# ButtonsLEDs.net
KiCad netlist of a schematic drawn in EAGLE
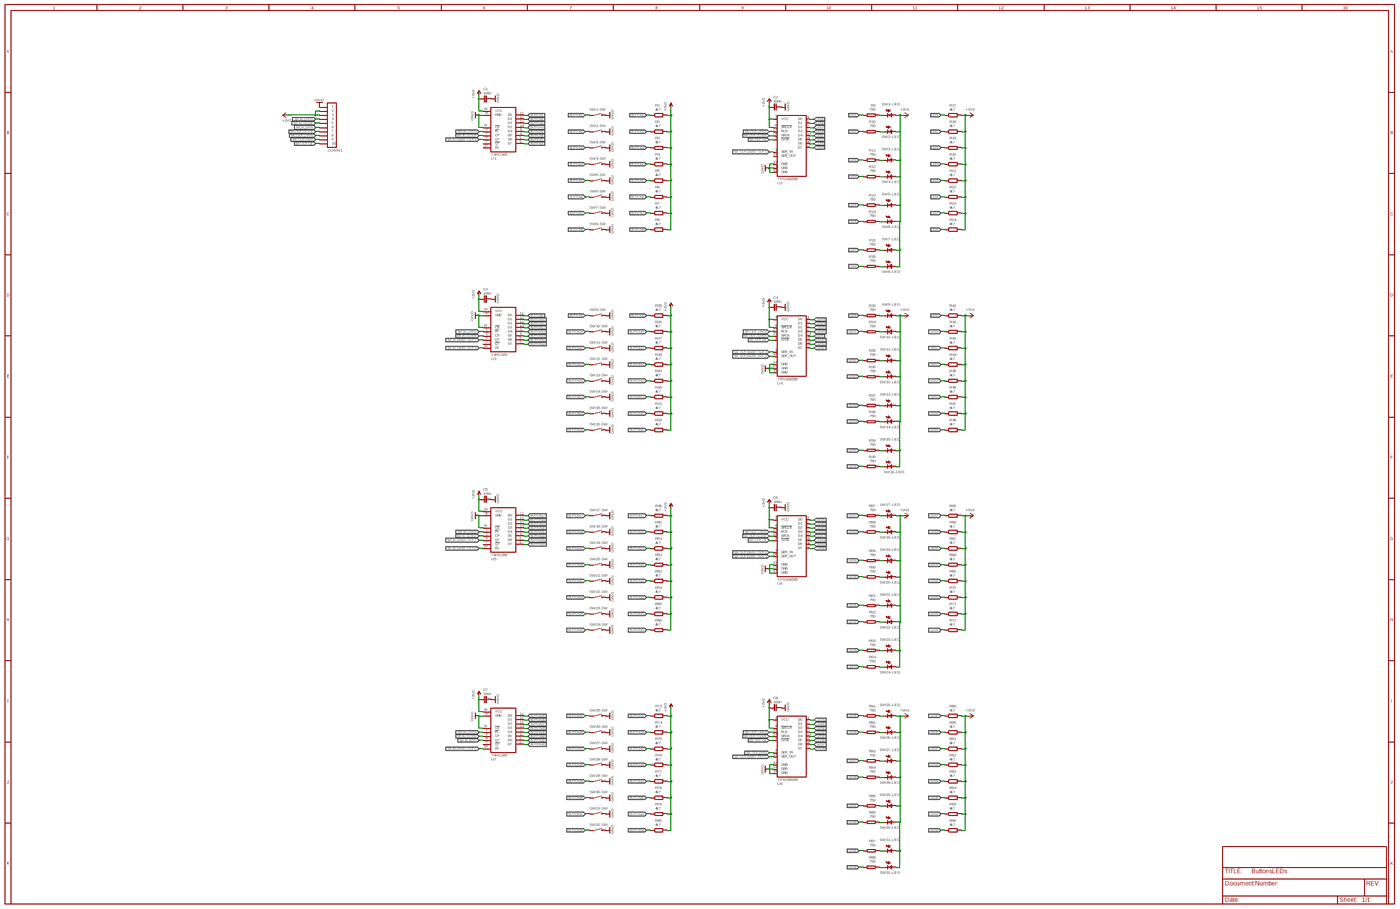
[diagram p0: schematic, sheet 1, overview]
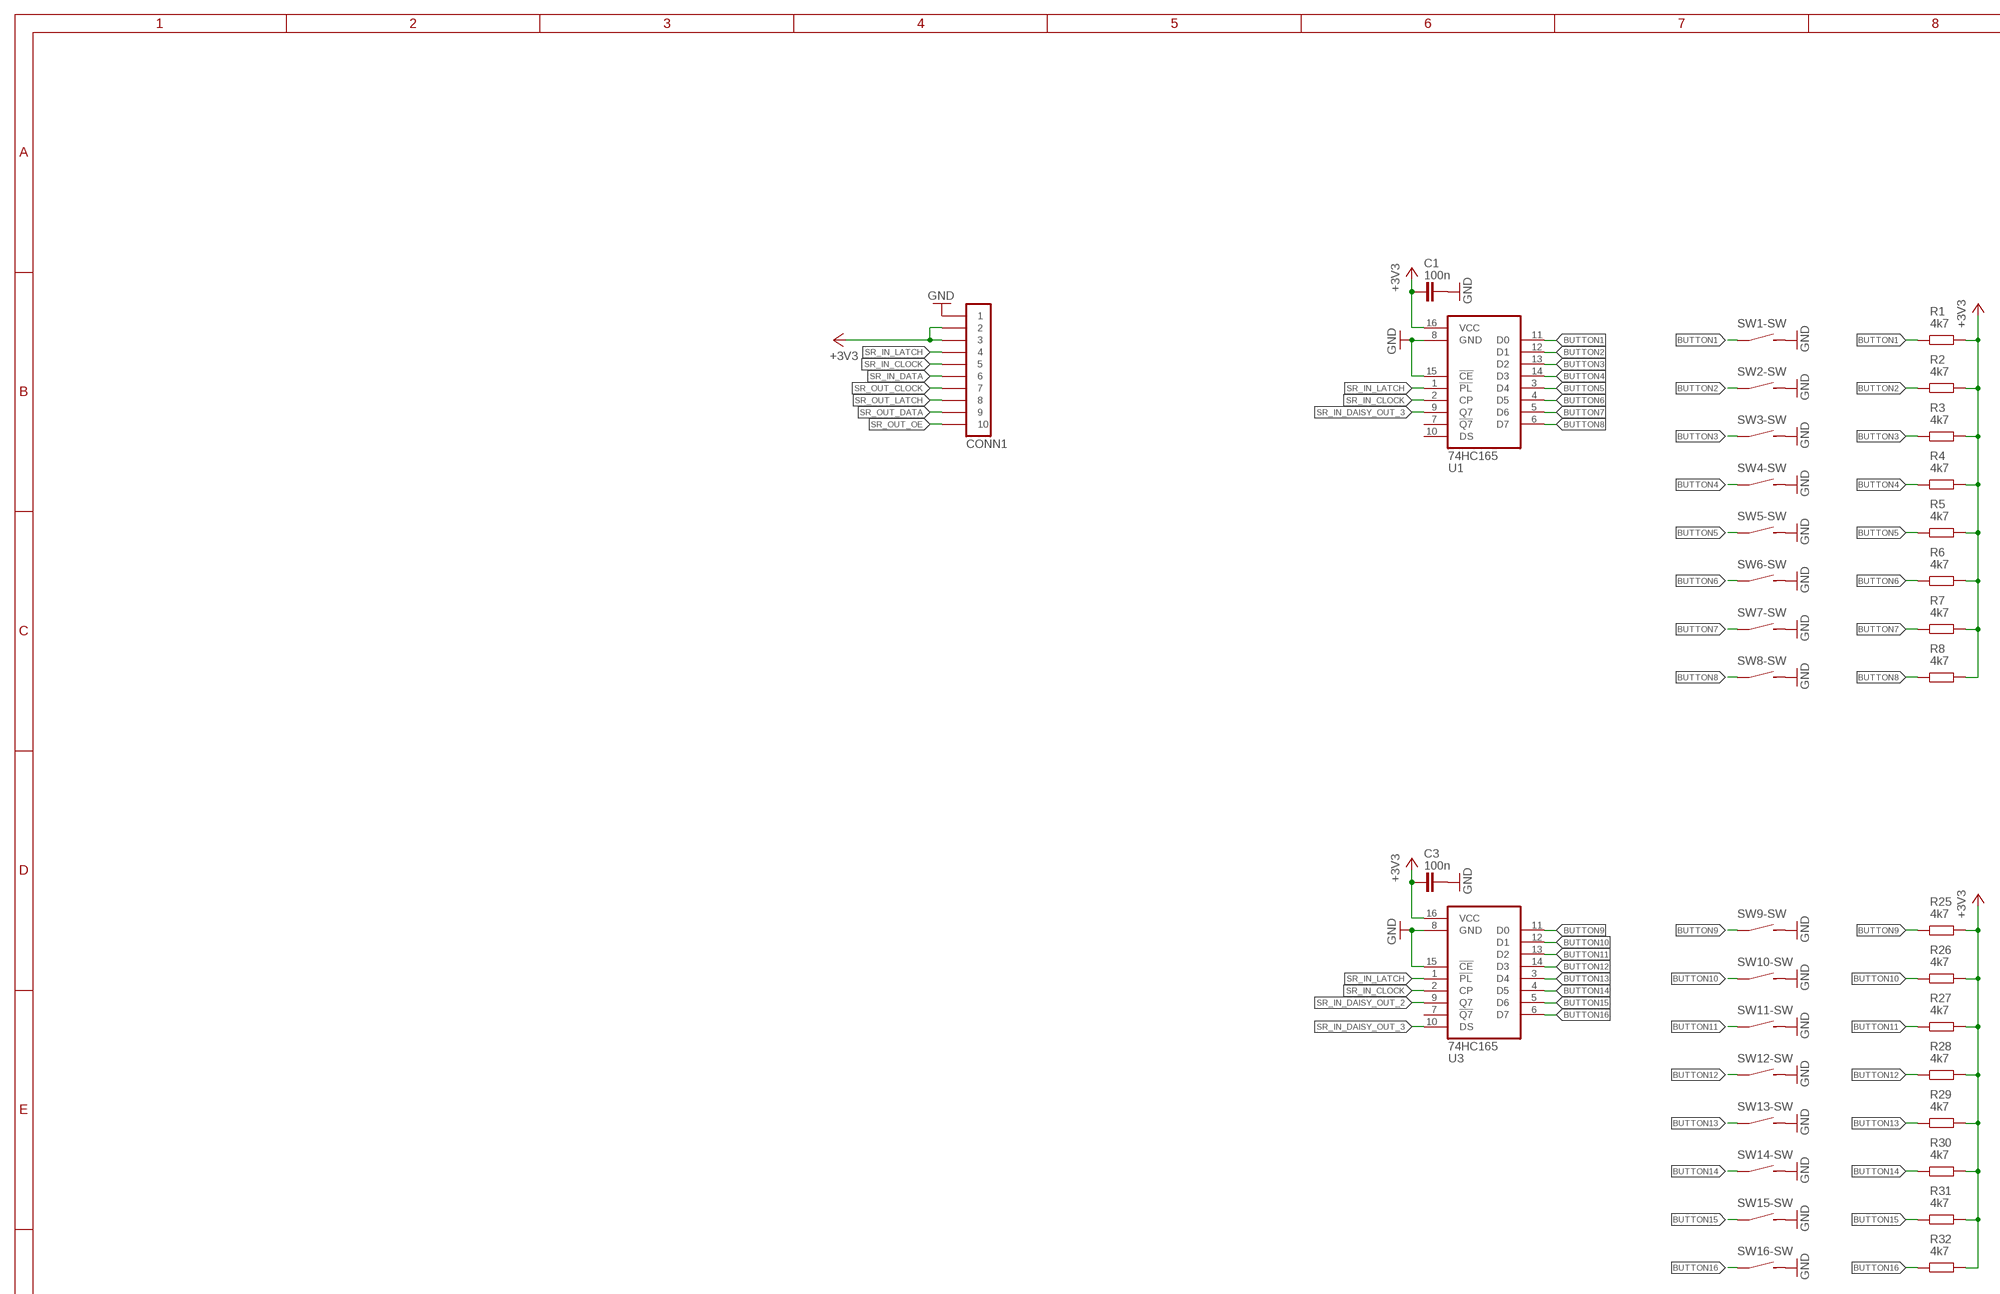
[diagram p1: schematic, sheet 1, part 1 of 4]
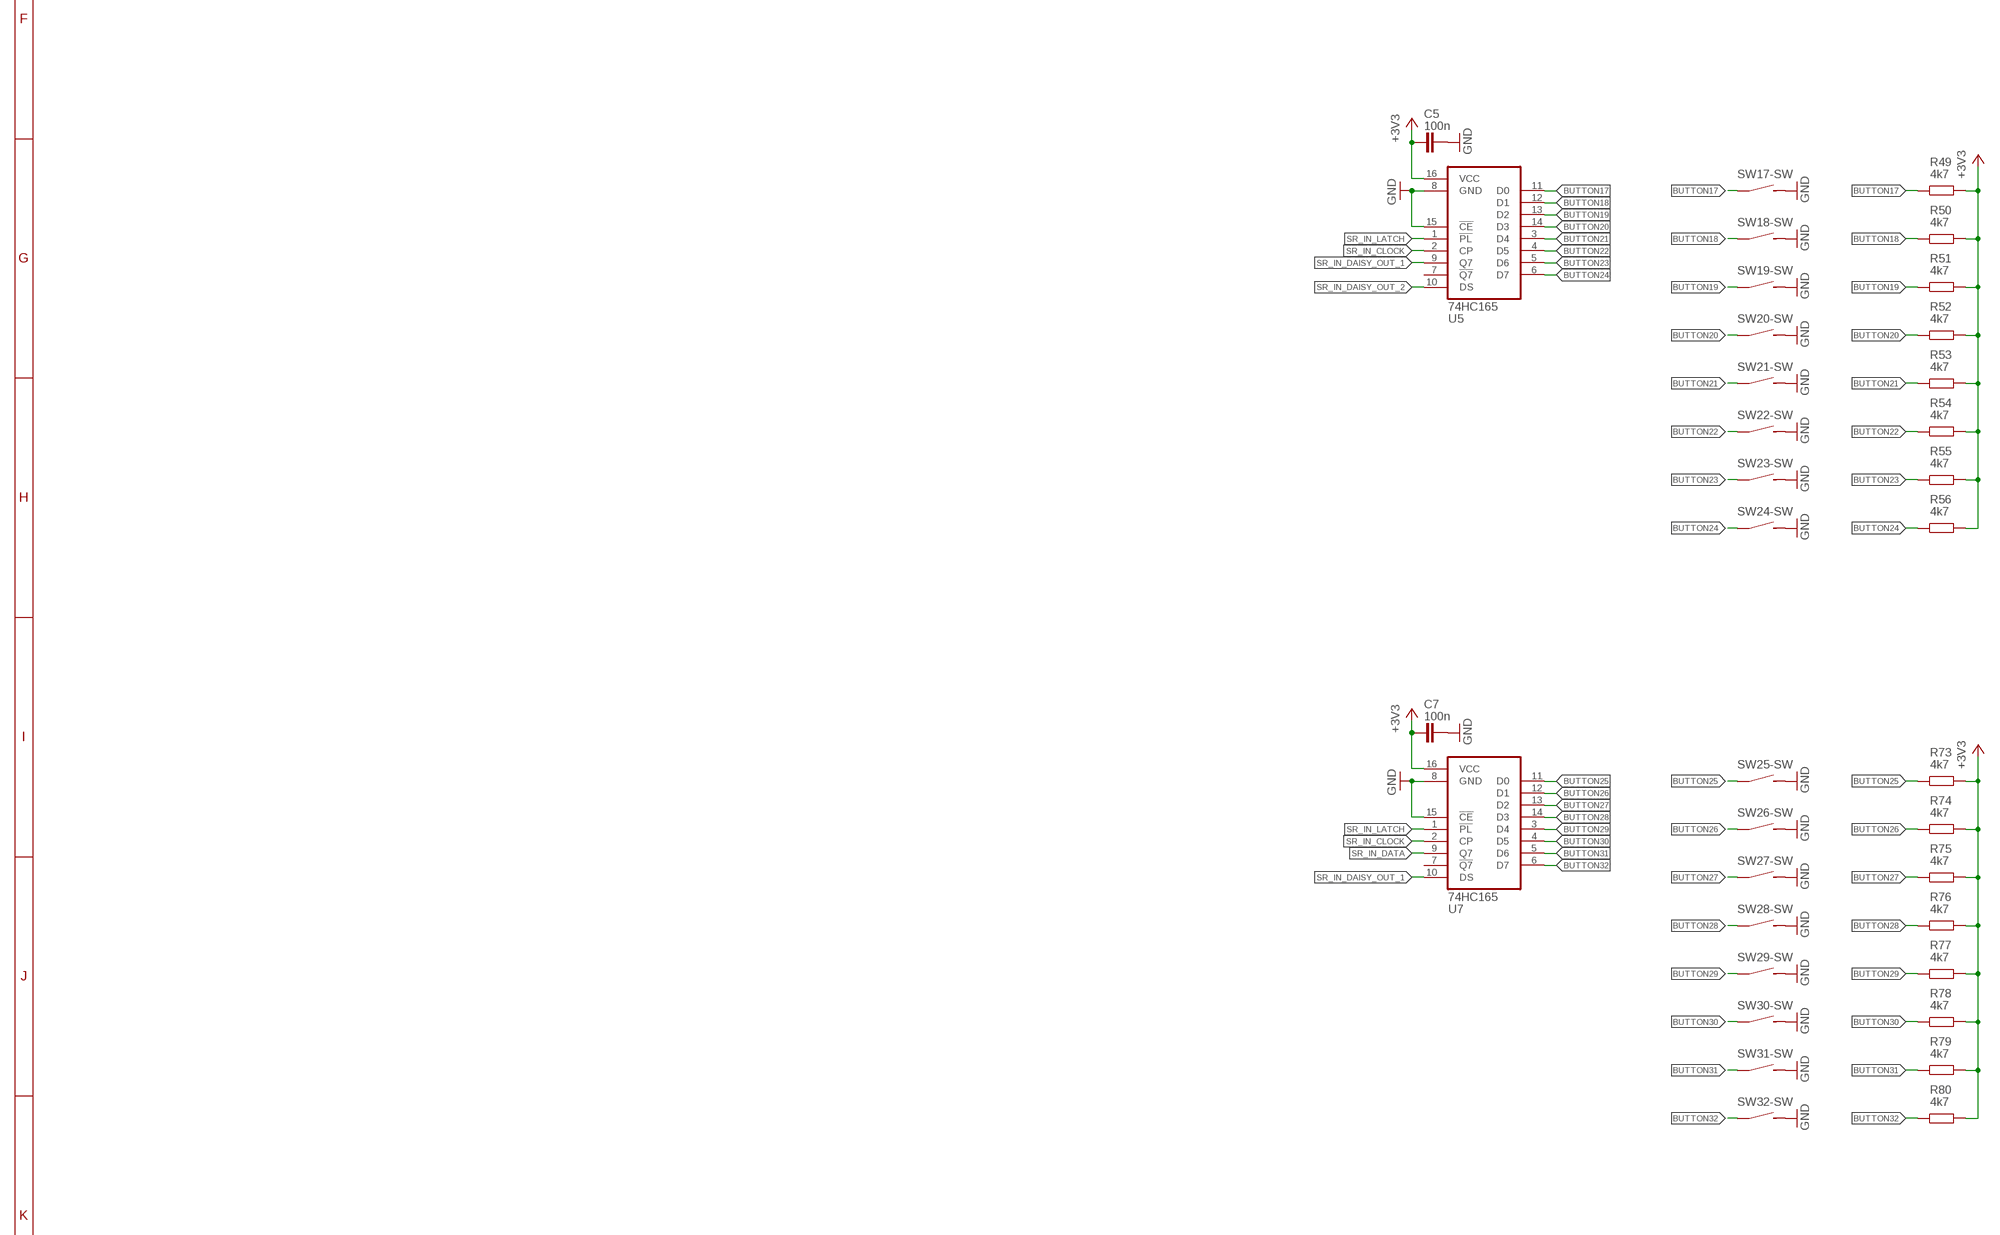
[diagram p2: schematic, sheet 1, part 2 of 4]
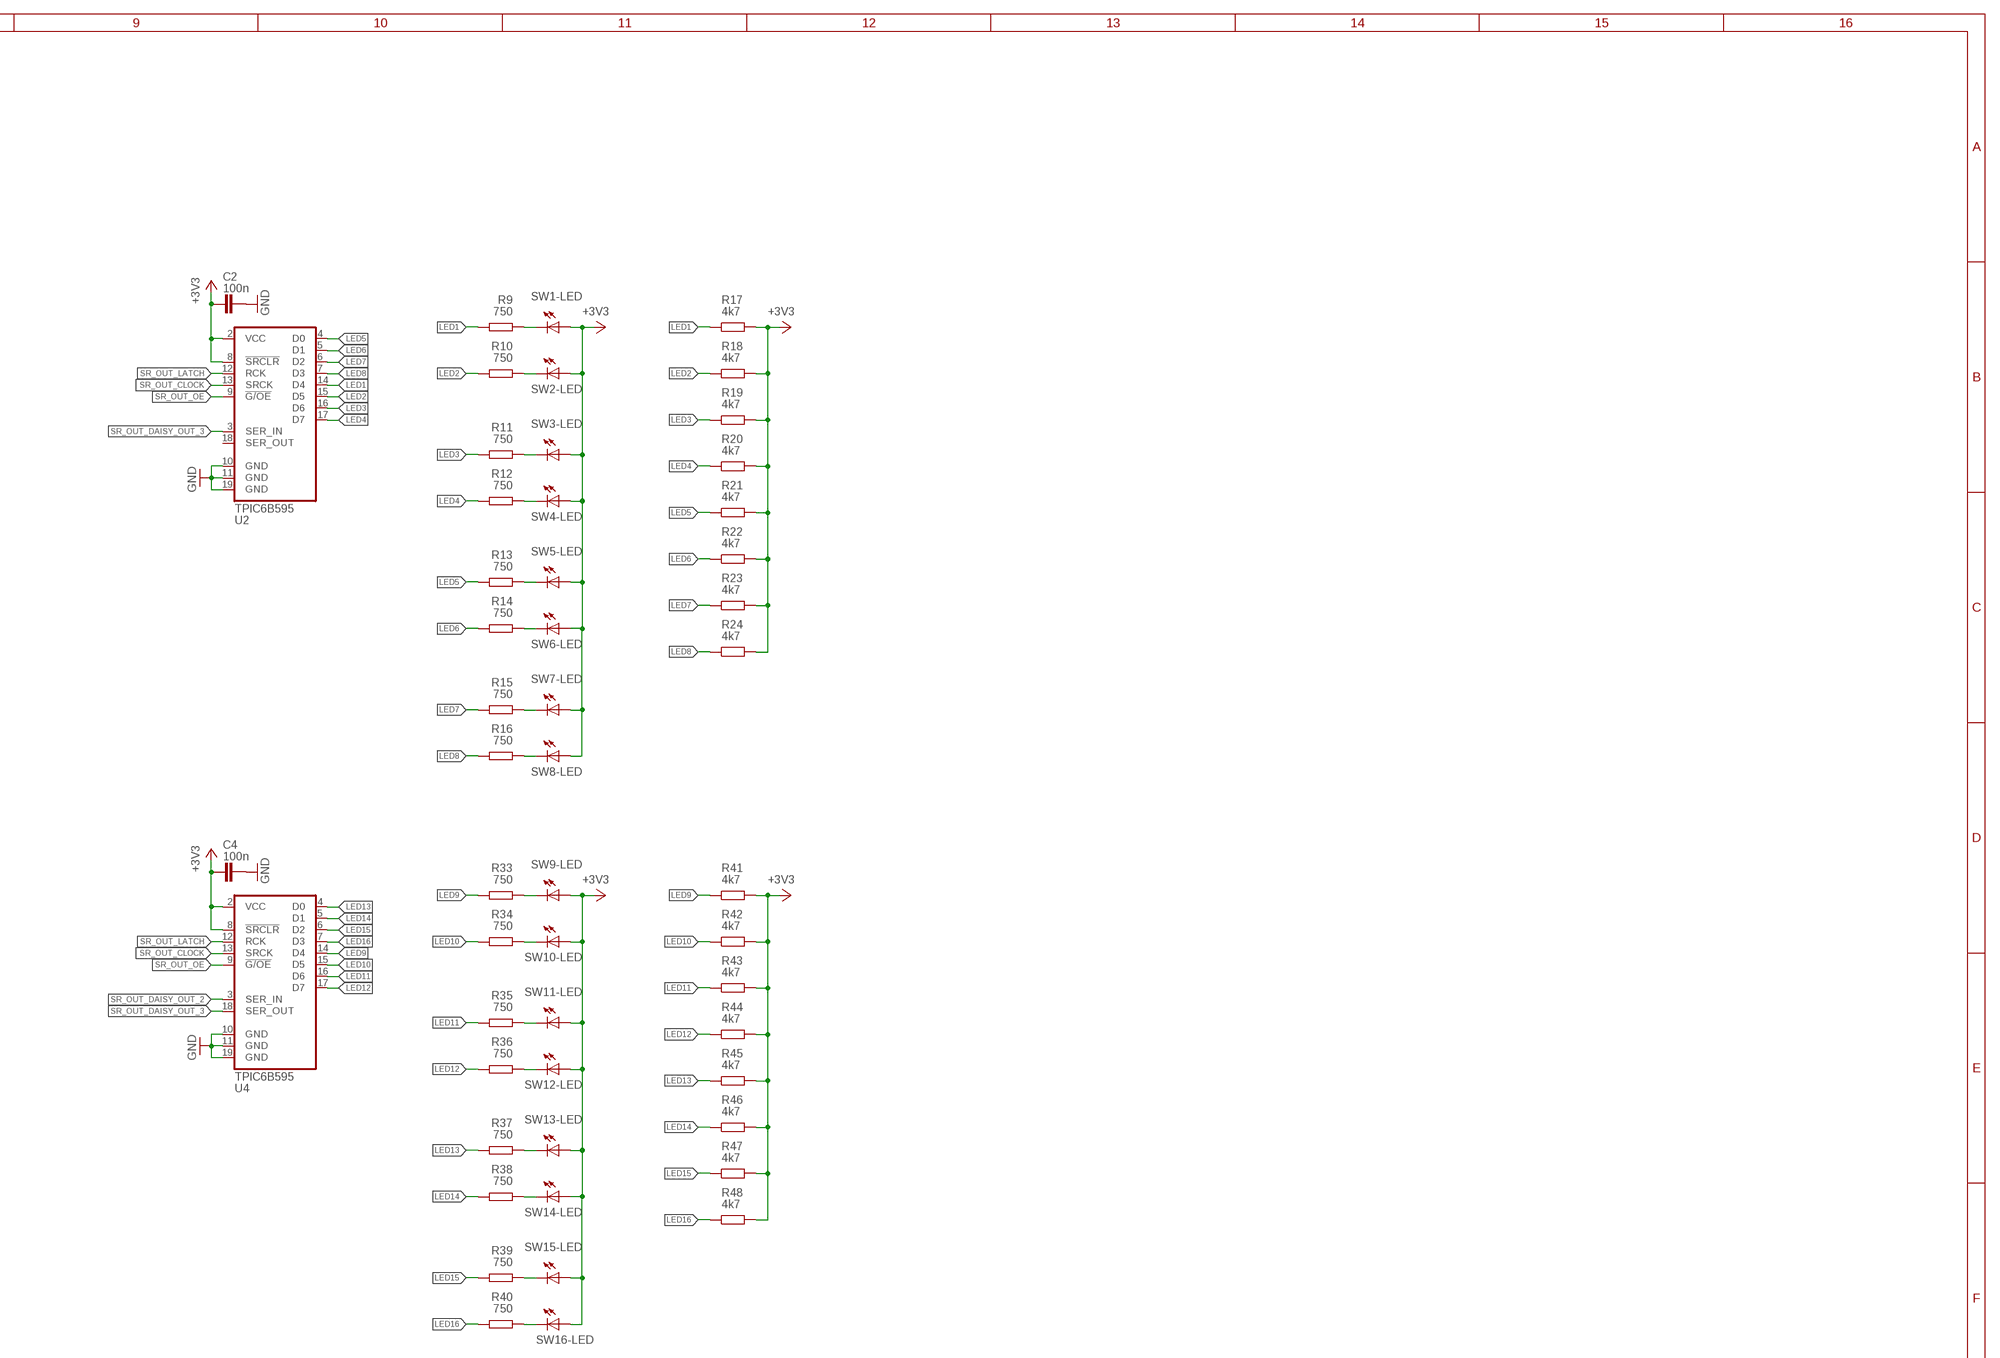
[diagram p3: schematic, sheet 1, part 3 of 4]
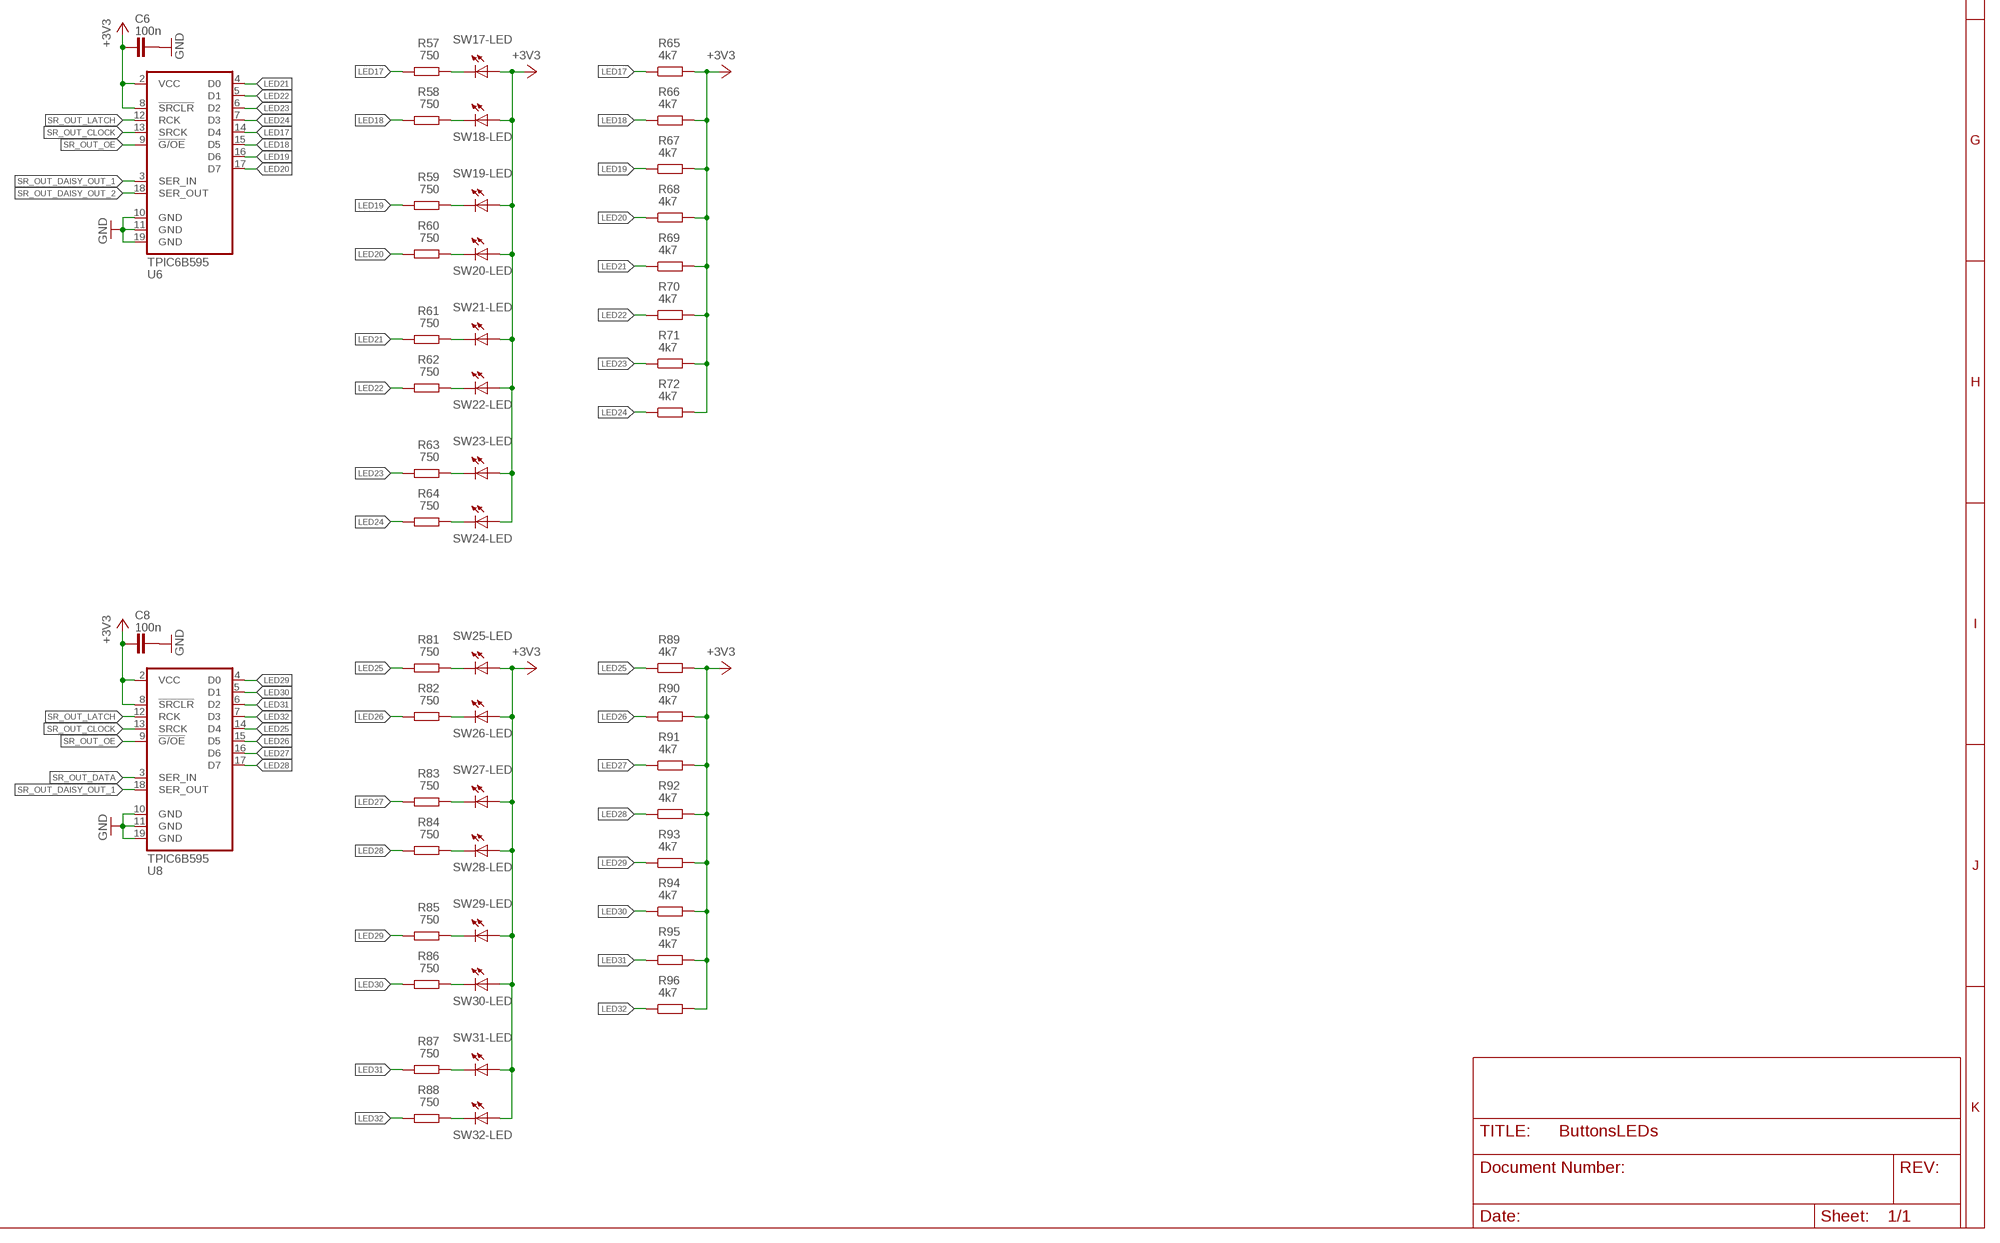
[diagram p4: schematic, sheet 1, part 4 of 4]

(export (version "E")
  (design (tool "Eeschema 10.0.6"))
  (components
    (comp (ref "C1")
      (value "100n")
      (footprint "eagle-import:C0805")
      (libsource (lib "eagle-import") (part "CAPACITOR-0805"))
    )
    (comp (ref "C2")
      (value "100n")
      (footprint "eagle-import:C0805")
      (libsource (lib "eagle-import") (part "CAPACITOR-0805"))
    )
    (comp (ref "C3")
      (value "100n")
      (footprint "eagle-import:C0805")
      (libsource (lib "eagle-import") (part "CAPACITOR-0805"))
    )
    (comp (ref "C4")
      (value "100n")
      (footprint "eagle-import:C0805")
      (libsource (lib "eagle-import") (part "CAPACITOR-0805"))
    )
    (comp (ref "C5")
      (value "100n")
      (footprint "eagle-import:C0805")
      (libsource (lib "eagle-import") (part "CAPACITOR-0805"))
    )
    (comp (ref "C6")
      (value "100n")
      (footprint "eagle-import:C0805")
      (libsource (lib "eagle-import") (part "CAPACITOR-0805"))
    )
    (comp (ref "C7")
      (value "100n")
      (footprint "eagle-import:C0805")
      (libsource (lib "eagle-import") (part "CAPACITOR-0805"))
    )
    (comp (ref "C8")
      (value "100n")
      (footprint "eagle-import:C0805")
      (libsource (lib "eagle-import") (part "CAPACITOR-0805"))
    )
    (comp (ref "CONN1")
      (value "PINHD-1X10-FFC-1MM-Z")
      (footprint "eagle-import:MOLEX-52271-1079")
      (fields (field (name "MANUFACTURER") "Molex") (field (name "MPN") "52271-1079"))
      (libsource (lib "eagle-import") (part "PINHD-1X10-FFC-1MM-Z"))
    )
    (comp (ref "R1")
      (value "4k7")
      (footprint "eagle-import:R0805")
      (libsource (lib "eagle-import") (part "RESISTOR-0805"))
    )
    (comp (ref "R2")
      (value "4k7")
      (footprint "eagle-import:R0805")
      (libsource (lib "eagle-import") (part "RESISTOR-0805"))
    )
    (comp (ref "R3")
      (value "4k7")
      (footprint "eagle-import:R0805")
      (libsource (lib "eagle-import") (part "RESISTOR-0805"))
    )
    (comp (ref "R4")
      (value "4k7")
      (footprint "eagle-import:R0805")
      (libsource (lib "eagle-import") (part "RESISTOR-0805"))
    )
    (comp (ref "R5")
      (value "4k7")
      (footprint "eagle-import:R0805")
      (libsource (lib "eagle-import") (part "RESISTOR-0805"))
    )
    (comp (ref "R6")
      (value "4k7")
      (footprint "eagle-import:R0805")
      (libsource (lib "eagle-import") (part "RESISTOR-0805"))
    )
    (comp (ref "R7")
      (value "4k7")
      (footprint "eagle-import:R0805")
      (libsource (lib "eagle-import") (part "RESISTOR-0805"))
    )
    (comp (ref "R8")
      (value "4k7")
      (footprint "eagle-import:R0805")
      (libsource (lib "eagle-import") (part "RESISTOR-0805"))
    )
    (comp (ref "R9")
      (value "750")
      (footprint "eagle-import:R0805")
      (libsource (lib "eagle-import") (part "RESISTOR-0805"))
    )
    (comp (ref "R10")
      (value "750")
      (footprint "eagle-import:R0805")
      (libsource (lib "eagle-import") (part "RESISTOR-0805"))
    )
    (comp (ref "R11")
      (value "750")
      (footprint "eagle-import:R0805")
      (libsource (lib "eagle-import") (part "RESISTOR-0805"))
    )
    (comp (ref "R12")
      (value "750")
      (footprint "eagle-import:R0805")
      (libsource (lib "eagle-import") (part "RESISTOR-0805"))
    )
    (comp (ref "R13")
      (value "750")
      (footprint "eagle-import:R0805")
      (libsource (lib "eagle-import") (part "RESISTOR-0805"))
    )
    (comp (ref "R14")
      (value "750")
      (footprint "eagle-import:R0805")
      (libsource (lib "eagle-import") (part "RESISTOR-0805"))
    )
    (comp (ref "R15")
      (value "750")
      (footprint "eagle-import:R0805")
      (libsource (lib "eagle-import") (part "RESISTOR-0805"))
    )
    (comp (ref "R16")
      (value "750")
      (footprint "eagle-import:R0805")
      (libsource (lib "eagle-import") (part "RESISTOR-0805"))
    )
    (comp (ref "R17")
      (value "4k7")
      (footprint "eagle-import:R0805")
      (libsource (lib "eagle-import") (part "RESISTOR-0805"))
    )
    (comp (ref "R18")
      (value "4k7")
      (footprint "eagle-import:R0805")
      (libsource (lib "eagle-import") (part "RESISTOR-0805"))
    )
    (comp (ref "R19")
      (value "4k7")
      (footprint "eagle-import:R0805")
      (libsource (lib "eagle-import") (part "RESISTOR-0805"))
    )
    (comp (ref "R20")
      (value "4k7")
      (footprint "eagle-import:R0805")
      (libsource (lib "eagle-import") (part "RESISTOR-0805"))
    )
    (comp (ref "R21")
      (value "4k7")
      (footprint "eagle-import:R0805")
      (libsource (lib "eagle-import") (part "RESISTOR-0805"))
    )
    (comp (ref "R22")
      (value "4k7")
      (footprint "eagle-import:R0805")
      (libsource (lib "eagle-import") (part "RESISTOR-0805"))
    )
    (comp (ref "R23")
      (value "4k7")
      (footprint "eagle-import:R0805")
      (libsource (lib "eagle-import") (part "RESISTOR-0805"))
    )
    (comp (ref "R24")
      (value "4k7")
      (footprint "eagle-import:R0805")
      (libsource (lib "eagle-import") (part "RESISTOR-0805"))
    )
    (comp (ref "R25")
      (value "4k7")
      (footprint "eagle-import:R0805")
      (libsource (lib "eagle-import") (part "RESISTOR-0805"))
    )
    (comp (ref "R26")
      (value "4k7")
      (footprint "eagle-import:R0805")
      (libsource (lib "eagle-import") (part "RESISTOR-0805"))
    )
    (comp (ref "R27")
      (value "4k7")
      (footprint "eagle-import:R0805")
      (libsource (lib "eagle-import") (part "RESISTOR-0805"))
    )
    (comp (ref "R28")
      (value "4k7")
      (footprint "eagle-import:R0805")
      (libsource (lib "eagle-import") (part "RESISTOR-0805"))
    )
    (comp (ref "R29")
      (value "4k7")
      (footprint "eagle-import:R0805")
      (libsource (lib "eagle-import") (part "RESISTOR-0805"))
    )
    (comp (ref "R30")
      (value "4k7")
      (footprint "eagle-import:R0805")
      (libsource (lib "eagle-import") (part "RESISTOR-0805"))
    )
    (comp (ref "R31")
      (value "4k7")
      (footprint "eagle-import:R0805")
      (libsource (lib "eagle-import") (part "RESISTOR-0805"))
    )
    (comp (ref "R32")
      (value "4k7")
      (footprint "eagle-import:R0805")
      (libsource (lib "eagle-import") (part "RESISTOR-0805"))
    )
    (comp (ref "R33")
      (value "750")
      (footprint "eagle-import:R0805")
      (libsource (lib "eagle-import") (part "RESISTOR-0805"))
    )
    (comp (ref "R34")
      (value "750")
      (footprint "eagle-import:R0805")
      (libsource (lib "eagle-import") (part "RESISTOR-0805"))
    )
    (comp (ref "R35")
      (value "750")
      (footprint "eagle-import:R0805")
      (libsource (lib "eagle-import") (part "RESISTOR-0805"))
    )
    (comp (ref "R36")
      (value "750")
      (footprint "eagle-import:R0805")
      (libsource (lib "eagle-import") (part "RESISTOR-0805"))
    )
    (comp (ref "R37")
      (value "750")
      (footprint "eagle-import:R0805")
      (libsource (lib "eagle-import") (part "RESISTOR-0805"))
    )
    (comp (ref "R38")
      (value "750")
      (footprint "eagle-import:R0805")
      (libsource (lib "eagle-import") (part "RESISTOR-0805"))
    )
    (comp (ref "R39")
      (value "750")
      (footprint "eagle-import:R0805")
      (libsource (lib "eagle-import") (part "RESISTOR-0805"))
    )
    (comp (ref "R40")
      (value "750")
      (footprint "eagle-import:R0805")
      (libsource (lib "eagle-import") (part "RESISTOR-0805"))
    )
    (comp (ref "R41")
      (value "4k7")
      (footprint "eagle-import:R0805")
      (libsource (lib "eagle-import") (part "RESISTOR-0805"))
    )
    (comp (ref "R42")
      (value "4k7")
      (footprint "eagle-import:R0805")
      (libsource (lib "eagle-import") (part "RESISTOR-0805"))
    )
    (comp (ref "R43")
      (value "4k7")
      (footprint "eagle-import:R0805")
      (libsource (lib "eagle-import") (part "RESISTOR-0805"))
    )
    (comp (ref "R44")
      (value "4k7")
      (footprint "eagle-import:R0805")
      (libsource (lib "eagle-import") (part "RESISTOR-0805"))
    )
    (comp (ref "R45")
      (value "4k7")
      (footprint "eagle-import:R0805")
      (libsource (lib "eagle-import") (part "RESISTOR-0805"))
    )
    (comp (ref "R46")
      (value "4k7")
      (footprint "eagle-import:R0805")
      (libsource (lib "eagle-import") (part "RESISTOR-0805"))
    )
    (comp (ref "R47")
      (value "4k7")
      (footprint "eagle-import:R0805")
      (libsource (lib "eagle-import") (part "RESISTOR-0805"))
    )
    (comp (ref "R48")
      (value "4k7")
      (footprint "eagle-import:R0805")
      (libsource (lib "eagle-import") (part "RESISTOR-0805"))
    )
    (comp (ref "R49")
      (value "4k7")
      (footprint "eagle-import:R0805")
      (libsource (lib "eagle-import") (part "RESISTOR-0805"))
    )
    (comp (ref "R50")
      (value "4k7")
      (footprint "eagle-import:R0805")
      (libsource (lib "eagle-import") (part "RESISTOR-0805"))
    )
    (comp (ref "R51")
      (value "4k7")
      (footprint "eagle-import:R0805")
      (libsource (lib "eagle-import") (part "RESISTOR-0805"))
    )
    (comp (ref "R52")
      (value "4k7")
      (footprint "eagle-import:R0805")
      (libsource (lib "eagle-import") (part "RESISTOR-0805"))
    )
    (comp (ref "R53")
      (value "4k7")
      (footprint "eagle-import:R0805")
      (libsource (lib "eagle-import") (part "RESISTOR-0805"))
    )
    (comp (ref "R54")
      (value "4k7")
      (footprint "eagle-import:R0805")
      (libsource (lib "eagle-import") (part "RESISTOR-0805"))
    )
    (comp (ref "R55")
      (value "4k7")
      (footprint "eagle-import:R0805")
      (libsource (lib "eagle-import") (part "RESISTOR-0805"))
    )
    (comp (ref "R56")
      (value "4k7")
      (footprint "eagle-import:R0805")
      (libsource (lib "eagle-import") (part "RESISTOR-0805"))
    )
    (comp (ref "R57")
      (value "750")
      (footprint "eagle-import:R0805")
      (libsource (lib "eagle-import") (part "RESISTOR-0805"))
    )
    (comp (ref "R58")
      (value "750")
      (footprint "eagle-import:R0805")
      (libsource (lib "eagle-import") (part "RESISTOR-0805"))
    )
    (comp (ref "R59")
      (value "750")
      (footprint "eagle-import:R0805")
      (libsource (lib "eagle-import") (part "RESISTOR-0805"))
    )
    (comp (ref "R60")
      (value "750")
      (footprint "eagle-import:R0805")
      (libsource (lib "eagle-import") (part "RESISTOR-0805"))
    )
    (comp (ref "R61")
      (value "750")
      (footprint "eagle-import:R0805")
      (libsource (lib "eagle-import") (part "RESISTOR-0805"))
    )
    (comp (ref "R62")
      (value "750")
      (footprint "eagle-import:R0805")
      (libsource (lib "eagle-import") (part "RESISTOR-0805"))
    )
    (comp (ref "R63")
      (value "750")
      (footprint "eagle-import:R0805")
      (libsource (lib "eagle-import") (part "RESISTOR-0805"))
    )
    (comp (ref "R64")
      (value "750")
      (footprint "eagle-import:R0805")
      (libsource (lib "eagle-import") (part "RESISTOR-0805"))
    )
    (comp (ref "R65")
      (value "4k7")
      (footprint "eagle-import:R0805")
      (libsource (lib "eagle-import") (part "RESISTOR-0805"))
    )
    (comp (ref "R66")
      (value "4k7")
      (footprint "eagle-import:R0805")
      (libsource (lib "eagle-import") (part "RESISTOR-0805"))
    )
    (comp (ref "R67")
      (value "4k7")
      (footprint "eagle-import:R0805")
      (libsource (lib "eagle-import") (part "RESISTOR-0805"))
    )
    (comp (ref "R68")
      (value "4k7")
      (footprint "eagle-import:R0805")
      (libsource (lib "eagle-import") (part "RESISTOR-0805"))
    )
    (comp (ref "R69")
      (value "4k7")
      (footprint "eagle-import:R0805")
      (libsource (lib "eagle-import") (part "RESISTOR-0805"))
    )
    (comp (ref "R70")
      (value "4k7")
      (footprint "eagle-import:R0805")
      (libsource (lib "eagle-import") (part "RESISTOR-0805"))
    )
    (comp (ref "R71")
      (value "4k7")
      (footprint "eagle-import:R0805")
      (libsource (lib "eagle-import") (part "RESISTOR-0805"))
    )
    (comp (ref "R72")
      (value "4k7")
      (footprint "eagle-import:R0805")
      (libsource (lib "eagle-import") (part "RESISTOR-0805"))
    )
    (comp (ref "R73")
      (value "4k7")
      (footprint "eagle-import:R0805")
      (libsource (lib "eagle-import") (part "RESISTOR-0805"))
    )
    (comp (ref "R74")
      (value "4k7")
      (footprint "eagle-import:R0805")
      (libsource (lib "eagle-import") (part "RESISTOR-0805"))
    )
    (comp (ref "R75")
      (value "4k7")
      (footprint "eagle-import:R0805")
      (libsource (lib "eagle-import") (part "RESISTOR-0805"))
    )
    (comp (ref "R76")
      (value "4k7")
      (footprint "eagle-import:R0805")
      (libsource (lib "eagle-import") (part "RESISTOR-0805"))
    )
    (comp (ref "R77")
      (value "4k7")
      (footprint "eagle-import:R0805")
      (libsource (lib "eagle-import") (part "RESISTOR-0805"))
    )
    (comp (ref "R78")
      (value "4k7")
      (footprint "eagle-import:R0805")
      (libsource (lib "eagle-import") (part "RESISTOR-0805"))
    )
    (comp (ref "R79")
      (value "4k7")
      (footprint "eagle-import:R0805")
      (libsource (lib "eagle-import") (part "RESISTOR-0805"))
    )
    (comp (ref "R80")
      (value "4k7")
      (footprint "eagle-import:R0805")
      (libsource (lib "eagle-import") (part "RESISTOR-0805"))
    )
    (comp (ref "R81")
      (value "750")
      (footprint "eagle-import:R0805")
      (libsource (lib "eagle-import") (part "RESISTOR-0805"))
    )
    (comp (ref "R82")
      (value "750")
      (footprint "eagle-import:R0805")
      (libsource (lib "eagle-import") (part "RESISTOR-0805"))
    )
    (comp (ref "R83")
      (value "750")
      (footprint "eagle-import:R0805")
      (libsource (lib "eagle-import") (part "RESISTOR-0805"))
    )
    (comp (ref "R84")
      (value "750")
      (footprint "eagle-import:R0805")
      (libsource (lib "eagle-import") (part "RESISTOR-0805"))
    )
    (comp (ref "R85")
      (value "750")
      (footprint "eagle-import:R0805")
      (libsource (lib "eagle-import") (part "RESISTOR-0805"))
    )
    (comp (ref "R86")
      (value "750")
      (footprint "eagle-import:R0805")
      (libsource (lib "eagle-import") (part "RESISTOR-0805"))
    )
    (comp (ref "R87")
      (value "750")
      (footprint "eagle-import:R0805")
      (libsource (lib "eagle-import") (part "RESISTOR-0805"))
    )
    (comp (ref "R88")
      (value "750")
      (footprint "eagle-import:R0805")
      (libsource (lib "eagle-import") (part "RESISTOR-0805"))
    )
    (comp (ref "R89")
      (value "4k7")
      (footprint "eagle-import:R0805")
      (libsource (lib "eagle-import") (part "RESISTOR-0805"))
    )
    (comp (ref "R90")
      (value "4k7")
      (footprint "eagle-import:R0805")
      (libsource (lib "eagle-import") (part "RESISTOR-0805"))
    )
    (comp (ref "R91")
      (value "4k7")
      (footprint "eagle-import:R0805")
      (libsource (lib "eagle-import") (part "RESISTOR-0805"))
    )
    (comp (ref "R92")
      (value "4k7")
      (footprint "eagle-import:R0805")
      (libsource (lib "eagle-import") (part "RESISTOR-0805"))
    )
    (comp (ref "R93")
      (value "4k7")
      (footprint "eagle-import:R0805")
      (libsource (lib "eagle-import") (part "RESISTOR-0805"))
    )
    (comp (ref "R94")
      (value "4k7")
      (footprint "eagle-import:R0805")
      (libsource (lib "eagle-import") (part "RESISTOR-0805"))
    )
    (comp (ref "R95")
      (value "4k7")
      (footprint "eagle-import:R0805")
      (libsource (lib "eagle-import") (part "RESISTOR-0805"))
    )
    (comp (ref "R96")
      (value "4k7")
      (footprint "eagle-import:R0805")
      (libsource (lib "eagle-import") (part "RESISTOR-0805"))
    )
    (comp (ref "SW1")
      (value "OMRON-B3W-9")
      (footprint "eagle-import:OMRON-B3W-9")
      (libsource (lib "eagle-import") (part "OMRON-B3W-9"))
    )
    (comp (ref "SW2")
      (value "OMRON-B3W-9")
      (footprint "eagle-import:OMRON-B3W-9")
      (libsource (lib "eagle-import") (part "OMRON-B3W-9"))
    )
    (comp (ref "SW3")
      (value "OMRON-B3W-9")
      (footprint "eagle-import:OMRON-B3W-9")
      (libsource (lib "eagle-import") (part "OMRON-B3W-9"))
    )
    (comp (ref "SW4")
      (value "OMRON-B3W-9")
      (footprint "eagle-import:OMRON-B3W-9")
      (libsource (lib "eagle-import") (part "OMRON-B3W-9"))
    )
    (comp (ref "SW5")
      (value "OMRON-B3W-9")
      (footprint "eagle-import:OMRON-B3W-9")
      (libsource (lib "eagle-import") (part "OMRON-B3W-9"))
    )
    (comp (ref "SW6")
      (value "OMRON-B3W-9")
      (footprint "eagle-import:OMRON-B3W-9")
      (libsource (lib "eagle-import") (part "OMRON-B3W-9"))
    )
    (comp (ref "SW7")
      (value "OMRON-B3W-9")
      (footprint "eagle-import:OMRON-B3W-9")
      (libsource (lib "eagle-import") (part "OMRON-B3W-9"))
    )
    (comp (ref "SW8")
      (value "OMRON-B3W-9")
      (footprint "eagle-import:OMRON-B3W-9")
      (libsource (lib "eagle-import") (part "OMRON-B3W-9"))
    )
    (comp (ref "SW9")
      (value "OMRON-B3W-9")
      (footprint "eagle-import:OMRON-B3W-9")
      (libsource (lib "eagle-import") (part "OMRON-B3W-9"))
    )
    (comp (ref "SW10")
      (value "OMRON-B3W-9")
      (footprint "eagle-import:OMRON-B3W-9")
      (libsource (lib "eagle-import") (part "OMRON-B3W-9"))
    )
    (comp (ref "SW11")
      (value "OMRON-B3W-9")
      (footprint "eagle-import:OMRON-B3W-9")
      (libsource (lib "eagle-import") (part "OMRON-B3W-9"))
    )
    (comp (ref "SW12")
      (value "OMRON-B3W-9")
      (footprint "eagle-import:OMRON-B3W-9")
      (libsource (lib "eagle-import") (part "OMRON-B3W-9"))
    )
    (comp (ref "SW13")
      (value "OMRON-B3W-9")
      (footprint "eagle-import:OMRON-B3W-9")
      (libsource (lib "eagle-import") (part "OMRON-B3W-9"))
    )
    (comp (ref "SW14")
      (value "OMRON-B3W-9")
      (footprint "eagle-import:OMRON-B3W-9")
      (libsource (lib "eagle-import") (part "OMRON-B3W-9"))
    )
    (comp (ref "SW15")
      (value "OMRON-B3W-9")
      (footprint "eagle-import:OMRON-B3W-9")
      (libsource (lib "eagle-import") (part "OMRON-B3W-9"))
    )
    (comp (ref "SW16")
      (value "OMRON-B3W-9")
      (footprint "eagle-import:OMRON-B3W-9")
      (libsource (lib "eagle-import") (part "OMRON-B3W-9"))
    )
    (comp (ref "SW17")
      (value "OMRON-B3W-9")
      (footprint "eagle-import:OMRON-B3W-9")
      (libsource (lib "eagle-import") (part "OMRON-B3W-9"))
    )
    (comp (ref "SW18")
      (value "OMRON-B3W-9")
      (footprint "eagle-import:OMRON-B3W-9")
      (libsource (lib "eagle-import") (part "OMRON-B3W-9"))
    )
    (comp (ref "SW19")
      (value "OMRON-B3W-9")
      (footprint "eagle-import:OMRON-B3W-9")
      (libsource (lib "eagle-import") (part "OMRON-B3W-9"))
    )
    (comp (ref "SW20")
      (value "OMRON-B3W-9")
      (footprint "eagle-import:OMRON-B3W-9")
      (libsource (lib "eagle-import") (part "OMRON-B3W-9"))
    )
    (comp (ref "SW21")
      (value "OMRON-B3W-9")
      (footprint "eagle-import:OMRON-B3W-9")
      (libsource (lib "eagle-import") (part "OMRON-B3W-9"))
    )
    (comp (ref "SW22")
      (value "OMRON-B3W-9")
      (footprint "eagle-import:OMRON-B3W-9")
      (libsource (lib "eagle-import") (part "OMRON-B3W-9"))
    )
    (comp (ref "SW23")
      (value "OMRON-B3W-9")
      (footprint "eagle-import:OMRON-B3W-9")
      (libsource (lib "eagle-import") (part "OMRON-B3W-9"))
    )
    (comp (ref "SW24")
      (value "OMRON-B3W-9")
      (footprint "eagle-import:OMRON-B3W-9")
      (libsource (lib "eagle-import") (part "OMRON-B3W-9"))
    )
    (comp (ref "SW25")
      (value "OMRON-B3W-9")
      (footprint "eagle-import:OMRON-B3W-9")
      (libsource (lib "eagle-import") (part "OMRON-B3W-9"))
    )
    (comp (ref "SW26")
      (value "OMRON-B3W-9")
      (footprint "eagle-import:OMRON-B3W-9")
      (libsource (lib "eagle-import") (part "OMRON-B3W-9"))
    )
    (comp (ref "SW27")
      (value "OMRON-B3W-9")
      (footprint "eagle-import:OMRON-B3W-9")
      (libsource (lib "eagle-import") (part "OMRON-B3W-9"))
    )
    (comp (ref "SW28")
      (value "OMRON-B3W-9")
      (footprint "eagle-import:OMRON-B3W-9")
      (libsource (lib "eagle-import") (part "OMRON-B3W-9"))
    )
    (comp (ref "SW29")
      (value "OMRON-B3W-9")
      (footprint "eagle-import:OMRON-B3W-9")
      (libsource (lib "eagle-import") (part "OMRON-B3W-9"))
    )
    (comp (ref "SW30")
      (value "OMRON-B3W-9")
      (footprint "eagle-import:OMRON-B3W-9")
      (libsource (lib "eagle-import") (part "OMRON-B3W-9"))
    )
    (comp (ref "SW31")
      (value "OMRON-B3W-9")
      (footprint "eagle-import:OMRON-B3W-9")
      (libsource (lib "eagle-import") (part "OMRON-B3W-9"))
    )
    (comp (ref "SW32")
      (value "OMRON-B3W-9")
      (footprint "eagle-import:OMRON-B3W-9")
      (libsource (lib "eagle-import") (part "OMRON-B3W-9"))
    )
    (comp (ref "U1")
      (value "74HC165")
      (footprint "eagle-import:SO16")
      (fields (field (name "MANUFACTURER") "Nexperia") (field (name "MPN") "74HC165D"))
      (libsource (lib "eagle-import") (part "74165HC"))
    )
    (comp (ref "U2")
      (value "TPIC6B595")
      (footprint "eagle-import:SOIC20")
      (libsource (lib "eagle-import") (part "TPIC6B595"))
    )
    (comp (ref "U3")
      (value "74HC165")
      (footprint "eagle-import:SO16")
      (fields (field (name "MANUFACTURER") "Nexperia") (field (name "MPN") "74HC165D"))
      (libsource (lib "eagle-import") (part "74165HC"))
    )
    (comp (ref "U4")
      (value "TPIC6B595")
      (footprint "eagle-import:SOIC20")
      (libsource (lib "eagle-import") (part "TPIC6B595"))
    )
    (comp (ref "U5")
      (value "74HC165")
      (footprint "eagle-import:SO16")
      (fields (field (name "MANUFACTURER") "Nexperia") (field (name "MPN") "74HC165D"))
      (libsource (lib "eagle-import") (part "74165HC"))
    )
    (comp (ref "U6")
      (value "TPIC6B595")
      (footprint "eagle-import:SOIC20")
      (libsource (lib "eagle-import") (part "TPIC6B595"))
    )
    (comp (ref "U7")
      (value "74HC165")
      (footprint "eagle-import:SO16")
      (fields (field (name "MANUFACTURER") "Nexperia") (field (name "MPN") "74HC165D"))
      (libsource (lib "eagle-import") (part "74165HC"))
    )
    (comp (ref "U8")
      (value "TPIC6B595")
      (footprint "eagle-import:SOIC20")
      (libsource (lib "eagle-import") (part "TPIC6B595"))
    )
  )
  (nets
    (net (code "1") (name "+3V3") (class "Default")
      (node (ref "C1") (pin "1") (pinfunction "1_1") (pintype "passive"))
      (node (ref "C2") (pin "1") (pinfunction "1_1") (pintype "passive"))
      (node (ref "C3") (pin "1") (pinfunction "1_1") (pintype "passive"))
      (node (ref "C4") (pin "1") (pinfunction "1_1") (pintype "passive"))
      (node (ref "C5") (pin "1") (pinfunction "1_1") (pintype "passive"))
      (node (ref "C6") (pin "1") (pinfunction "1_1") (pintype "passive"))
      (node (ref "C7") (pin "1") (pinfunction "1_1") (pintype "passive"))
      (node (ref "C8") (pin "1") (pinfunction "1_1") (pintype "passive"))
      (node (ref "CONN1") (pin "2") (pinfunction "2_2") (pintype "passive"))
      (node (ref "CONN1") (pin "3") (pinfunction "3_3") (pintype "passive"))
      (node (ref "R1") (pin "2") (pinfunction "2_2") (pintype "passive"))
      (node (ref "R17") (pin "2") (pinfunction "2_2") (pintype "passive"))
      (node (ref "R18") (pin "2") (pinfunction "2_2") (pintype "passive"))
      (node (ref "R19") (pin "2") (pinfunction "2_2") (pintype "passive"))
      (node (ref "R2") (pin "2") (pinfunction "2_2") (pintype "passive"))
      (node (ref "R20") (pin "2") (pinfunction "2_2") (pintype "passive"))
      (node (ref "R21") (pin "2") (pinfunction "2_2") (pintype "passive"))
      (node (ref "R22") (pin "2") (pinfunction "2_2") (pintype "passive"))
      (node (ref "R23") (pin "2") (pinfunction "2_2") (pintype "passive"))
      (node (ref "R24") (pin "2") (pinfunction "2_2") (pintype "passive"))
      (node (ref "R25") (pin "2") (pinfunction "2_2") (pintype "passive"))
      (node (ref "R26") (pin "2") (pinfunction "2_2") (pintype "passive"))
      (node (ref "R27") (pin "2") (pinfunction "2_2") (pintype "passive"))
      (node (ref "R28") (pin "2") (pinfunction "2_2") (pintype "passive"))
      (node (ref "R29") (pin "2") (pinfunction "2_2") (pintype "passive"))
      (node (ref "R3") (pin "2") (pinfunction "2_2") (pintype "passive"))
      (node (ref "R30") (pin "2") (pinfunction "2_2") (pintype "passive"))
      (node (ref "R31") (pin "2") (pinfunction "2_2") (pintype "passive"))
      (node (ref "R32") (pin "2") (pinfunction "2_2") (pintype "passive"))
      (node (ref "R4") (pin "2") (pinfunction "2_2") (pintype "passive"))
      (node (ref "R41") (pin "2") (pinfunction "2_2") (pintype "passive"))
      (node (ref "R42") (pin "2") (pinfunction "2_2") (pintype "passive"))
      (node (ref "R43") (pin "2") (pinfunction "2_2") (pintype "passive"))
      (node (ref "R44") (pin "2") (pinfunction "2_2") (pintype "passive"))
      (node (ref "R45") (pin "2") (pinfunction "2_2") (pintype "passive"))
      (node (ref "R46") (pin "2") (pinfunction "2_2") (pintype "passive"))
      (node (ref "R47") (pin "2") (pinfunction "2_2") (pintype "passive"))
      (node (ref "R48") (pin "2") (pinfunction "2_2") (pintype "passive"))
      (node (ref "R49") (pin "2") (pinfunction "2_2") (pintype "passive"))
      (node (ref "R5") (pin "2") (pinfunction "2_2") (pintype "passive"))
      (node (ref "R50") (pin "2") (pinfunction "2_2") (pintype "passive"))
      (node (ref "R51") (pin "2") (pinfunction "2_2") (pintype "passive"))
      (node (ref "R52") (pin "2") (pinfunction "2_2") (pintype "passive"))
      (node (ref "R53") (pin "2") (pinfunction "2_2") (pintype "passive"))
      (node (ref "R54") (pin "2") (pinfunction "2_2") (pintype "passive"))
      (node (ref "R55") (pin "2") (pinfunction "2_2") (pintype "passive"))
      (node (ref "R56") (pin "2") (pinfunction "2_2") (pintype "passive"))
      (node (ref "R6") (pin "2") (pinfunction "2_2") (pintype "passive"))
      (node (ref "R65") (pin "2") (pinfunction "2_2") (pintype "passive"))
      (node (ref "R66") (pin "2") (pinfunction "2_2") (pintype "passive"))
      (node (ref "R67") (pin "2") (pinfunction "2_2") (pintype "passive"))
      (node (ref "R68") (pin "2") (pinfunction "2_2") (pintype "passive"))
      (node (ref "R69") (pin "2") (pinfunction "2_2") (pintype "passive"))
      (node (ref "R7") (pin "2") (pinfunction "2_2") (pintype "passive"))
      (node (ref "R70") (pin "2") (pinfunction "2_2") (pintype "passive"))
      (node (ref "R71") (pin "2") (pinfunction "2_2") (pintype "passive"))
      (node (ref "R72") (pin "2") (pinfunction "2_2") (pintype "passive"))
      (node (ref "R73") (pin "2") (pinfunction "2_2") (pintype "passive"))
      (node (ref "R74") (pin "2") (pinfunction "2_2") (pintype "passive"))
      (node (ref "R75") (pin "2") (pinfunction "2_2") (pintype "passive"))
      (node (ref "R76") (pin "2") (pinfunction "2_2") (pintype "passive"))
      (node (ref "R77") (pin "2") (pinfunction "2_2") (pintype "passive"))
      (node (ref "R78") (pin "2") (pinfunction "2_2") (pintype "passive"))
      (node (ref "R79") (pin "2") (pinfunction "2_2") (pintype "passive"))
      (node (ref "R8") (pin "2") (pinfunction "2_2") (pintype "passive"))
      (node (ref "R80") (pin "2") (pinfunction "2_2") (pintype "passive"))
      (node (ref "R89") (pin "2") (pinfunction "2_2") (pintype "passive"))
      (node (ref "R90") (pin "2") (pinfunction "2_2") (pintype "passive"))
      (node (ref "R91") (pin "2") (pinfunction "2_2") (pintype "passive"))
      (node (ref "R92") (pin "2") (pinfunction "2_2") (pintype "passive"))
      (node (ref "R93") (pin "2") (pinfunction "2_2") (pintype "passive"))
      (node (ref "R94") (pin "2") (pinfunction "2_2") (pintype "passive"))
      (node (ref "R95") (pin "2") (pinfunction "2_2") (pintype "passive"))
      (node (ref "R96") (pin "2") (pinfunction "2_2") (pintype "passive"))
      (node (ref "SW1") (pin "6-A") (pinfunction "A_6-A") (pintype "passive"))
      (node (ref "SW10") (pin "6-A") (pinfunction "A_6-A") (pintype "passive"))
      (node (ref "SW11") (pin "6-A") (pinfunction "A_6-A") (pintype "passive"))
      (node (ref "SW12") (pin "6-A") (pinfunction "A_6-A") (pintype "passive"))
      (node (ref "SW13") (pin "6-A") (pinfunction "A_6-A") (pintype "passive"))
      (node (ref "SW14") (pin "6-A") (pinfunction "A_6-A") (pintype "passive"))
      (node (ref "SW15") (pin "6-A") (pinfunction "A_6-A") (pintype "passive"))
      (node (ref "SW16") (pin "6-A") (pinfunction "A_6-A") (pintype "passive"))
      (node (ref "SW17") (pin "6-A") (pinfunction "A_6-A") (pintype "passive"))
      (node (ref "SW18") (pin "6-A") (pinfunction "A_6-A") (pintype "passive"))
      (node (ref "SW19") (pin "6-A") (pinfunction "A_6-A") (pintype "passive"))
      (node (ref "SW2") (pin "6-A") (pinfunction "A_6-A") (pintype "passive"))
      (node (ref "SW20") (pin "6-A") (pinfunction "A_6-A") (pintype "passive"))
      (node (ref "SW21") (pin "6-A") (pinfunction "A_6-A") (pintype "passive"))
      (node (ref "SW22") (pin "6-A") (pinfunction "A_6-A") (pintype "passive"))
      (node (ref "SW23") (pin "6-A") (pinfunction "A_6-A") (pintype "passive"))
      (node (ref "SW24") (pin "6-A") (pinfunction "A_6-A") (pintype "passive"))
      (node (ref "SW25") (pin "6-A") (pinfunction "A_6-A") (pintype "passive"))
      (node (ref "SW26") (pin "6-A") (pinfunction "A_6-A") (pintype "passive"))
      (node (ref "SW27") (pin "6-A") (pinfunction "A_6-A") (pintype "passive"))
      (node (ref "SW28") (pin "6-A") (pinfunction "A_6-A") (pintype "passive"))
      (node (ref "SW29") (pin "6-A") (pinfunction "A_6-A") (pintype "passive"))
      (node (ref "SW3") (pin "6-A") (pinfunction "A_6-A") (pintype "passive"))
      (node (ref "SW30") (pin "6-A") (pinfunction "A_6-A") (pintype "passive"))
      (node (ref "SW31") (pin "6-A") (pinfunction "A_6-A") (pintype "passive"))
      (node (ref "SW32") (pin "6-A") (pinfunction "A_6-A") (pintype "passive"))
      (node (ref "SW4") (pin "6-A") (pinfunction "A_6-A") (pintype "passive"))
      (node (ref "SW5") (pin "6-A") (pinfunction "A_6-A") (pintype "passive"))
      (node (ref "SW6") (pin "6-A") (pinfunction "A_6-A") (pintype "passive"))
      (node (ref "SW7") (pin "6-A") (pinfunction "A_6-A") (pintype "passive"))
      (node (ref "SW8") (pin "6-A") (pinfunction "A_6-A") (pintype "passive"))
      (node (ref "SW9") (pin "6-A") (pinfunction "A_6-A") (pintype "passive"))
      (node (ref "U1") (pin "16") (pinfunction "VCC_16") (pintype "power_in"))
      (node (ref "U2") (pin "2") (pinfunction "VCC_2") (pintype "power_in"))
      (node (ref "U2") (pin "8") (pinfunction "~{SRCLR}_8") (pintype "input"))
      (node (ref "U3") (pin "16") (pinfunction "VCC_16") (pintype "power_in"))
      (node (ref "U4") (pin "2") (pinfunction "VCC_2") (pintype "power_in"))
      (node (ref "U4") (pin "8") (pinfunction "~{SRCLR}_8") (pintype "input"))
      (node (ref "U5") (pin "16") (pinfunction "VCC_16") (pintype "power_in"))
      (node (ref "U6") (pin "2") (pinfunction "VCC_2") (pintype "power_in"))
      (node (ref "U6") (pin "8") (pinfunction "~{SRCLR}_8") (pintype "input"))
      (node (ref "U7") (pin "16") (pinfunction "VCC_16") (pintype "power_in"))
      (node (ref "U8") (pin "2") (pinfunction "VCC_2") (pintype "power_in"))
      (node (ref "U8") (pin "8") (pinfunction "~{SRCLR}_8") (pintype "input"))
    )
    (net (code "2") (name "BUTTON1") (class "Default")
      (node (ref "R1") (pin "1") (pinfunction "1_1") (pintype "passive"))
      (node (ref "SW1") (pin "1") (pinfunction "1_1") (pintype "passive"))
      (node (ref "U1") (pin "11") (pinfunction "D0_11") (pintype "input"))
    )
    (net (code "3") (name "BUTTON2") (class "Default")
      (node (ref "R2") (pin "1") (pinfunction "1_1") (pintype "passive"))
      (node (ref "SW2") (pin "1") (pinfunction "1_1") (pintype "passive"))
      (node (ref "U1") (pin "12") (pinfunction "D1_12") (pintype "input"))
    )
    (net (code "4") (name "BUTTON3") (class "Default")
      (node (ref "R3") (pin "1") (pinfunction "1_1") (pintype "passive"))
      (node (ref "SW3") (pin "1") (pinfunction "1_1") (pintype "passive"))
      (node (ref "U1") (pin "13") (pinfunction "D2_13") (pintype "input"))
    )
    (net (code "5") (name "BUTTON4") (class "Default")
      (node (ref "R4") (pin "1") (pinfunction "1_1") (pintype "passive"))
      (node (ref "SW4") (pin "1") (pinfunction "1_1") (pintype "passive"))
      (node (ref "U1") (pin "14") (pinfunction "D3_14") (pintype "input"))
    )
    (net (code "6") (name "BUTTON5") (class "Default")
      (node (ref "R5") (pin "1") (pinfunction "1_1") (pintype "passive"))
      (node (ref "SW5") (pin "1") (pinfunction "1_1") (pintype "passive"))
      (node (ref "U1") (pin "3") (pinfunction "D4_3") (pintype "input"))
    )
    (net (code "7") (name "BUTTON6") (class "Default")
      (node (ref "R6") (pin "1") (pinfunction "1_1") (pintype "passive"))
      (node (ref "SW6") (pin "1") (pinfunction "1_1") (pintype "passive"))
      (node (ref "U1") (pin "4") (pinfunction "D5_4") (pintype "input"))
    )
    (net (code "8") (name "BUTTON7") (class "Default")
      (node (ref "R7") (pin "1") (pinfunction "1_1") (pintype "passive"))
      (node (ref "SW7") (pin "1") (pinfunction "1_1") (pintype "passive"))
      (node (ref "U1") (pin "5") (pinfunction "D6_5") (pintype "input"))
    )
    (net (code "9") (name "BUTTON8") (class "Default")
      (node (ref "R8") (pin "1") (pinfunction "1_1") (pintype "passive"))
      (node (ref "SW8") (pin "1") (pinfunction "1_1") (pintype "passive"))
      (node (ref "U1") (pin "6") (pinfunction "D7_6") (pintype "input"))
    )
    (net (code "10") (name "BUTTON9") (class "Default")
      (node (ref "R25") (pin "1") (pinfunction "1_1") (pintype "passive"))
      (node (ref "SW9") (pin "1") (pinfunction "1_1") (pintype "passive"))
      (node (ref "U3") (pin "11") (pinfunction "D0_11") (pintype "input"))
    )
    (net (code "11") (name "BUTTON10") (class "Default")
      (node (ref "R26") (pin "1") (pinfunction "1_1") (pintype "passive"))
      (node (ref "SW10") (pin "1") (pinfunction "1_1") (pintype "passive"))
      (node (ref "U3") (pin "12") (pinfunction "D1_12") (pintype "input"))
    )
    (net (code "12") (name "BUTTON11") (class "Default")
      (node (ref "R27") (pin "1") (pinfunction "1_1") (pintype "passive"))
      (node (ref "SW11") (pin "1") (pinfunction "1_1") (pintype "passive"))
      (node (ref "U3") (pin "13") (pinfunction "D2_13") (pintype "input"))
    )
    (net (code "13") (name "BUTTON12") (class "Default")
      (node (ref "R28") (pin "1") (pinfunction "1_1") (pintype "passive"))
      (node (ref "SW12") (pin "1") (pinfunction "1_1") (pintype "passive"))
      (node (ref "U3") (pin "14") (pinfunction "D3_14") (pintype "input"))
    )
    (net (code "14") (name "BUTTON13") (class "Default")
      (node (ref "R29") (pin "1") (pinfunction "1_1") (pintype "passive"))
      (node (ref "SW13") (pin "1") (pinfunction "1_1") (pintype "passive"))
      (node (ref "U3") (pin "3") (pinfunction "D4_3") (pintype "input"))
    )
    (net (code "15") (name "BUTTON14") (class "Default")
      (node (ref "R30") (pin "1") (pinfunction "1_1") (pintype "passive"))
      (node (ref "SW14") (pin "1") (pinfunction "1_1") (pintype "passive"))
      (node (ref "U3") (pin "4") (pinfunction "D5_4") (pintype "input"))
    )
    (net (code "16") (name "BUTTON15") (class "Default")
      (node (ref "R31") (pin "1") (pinfunction "1_1") (pintype "passive"))
      (node (ref "SW15") (pin "1") (pinfunction "1_1") (pintype "passive"))
      (node (ref "U3") (pin "5") (pinfunction "D6_5") (pintype "input"))
    )
    (net (code "17") (name "BUTTON16") (class "Default")
      (node (ref "R32") (pin "1") (pinfunction "1_1") (pintype "passive"))
      (node (ref "SW16") (pin "1") (pinfunction "1_1") (pintype "passive"))
      (node (ref "U3") (pin "6") (pinfunction "D7_6") (pintype "input"))
    )
    (net (code "18") (name "BUTTON17") (class "Default")
      (node (ref "R49") (pin "1") (pinfunction "1_1") (pintype "passive"))
      (node (ref "SW17") (pin "1") (pinfunction "1_1") (pintype "passive"))
      (node (ref "U5") (pin "11") (pinfunction "D0_11") (pintype "input"))
    )
    (net (code "19") (name "BUTTON18") (class "Default")
      (node (ref "R50") (pin "1") (pinfunction "1_1") (pintype "passive"))
      (node (ref "SW18") (pin "1") (pinfunction "1_1") (pintype "passive"))
      (node (ref "U5") (pin "12") (pinfunction "D1_12") (pintype "input"))
    )
    (net (code "20") (name "BUTTON19") (class "Default")
      (node (ref "R51") (pin "1") (pinfunction "1_1") (pintype "passive"))
      (node (ref "SW19") (pin "1") (pinfunction "1_1") (pintype "passive"))
      (node (ref "U5") (pin "13") (pinfunction "D2_13") (pintype "input"))
    )
    (net (code "21") (name "BUTTON20") (class "Default")
      (node (ref "R52") (pin "1") (pinfunction "1_1") (pintype "passive"))
      (node (ref "SW20") (pin "1") (pinfunction "1_1") (pintype "passive"))
      (node (ref "U5") (pin "14") (pinfunction "D3_14") (pintype "input"))
    )
    (net (code "22") (name "BUTTON21") (class "Default")
      (node (ref "R53") (pin "1") (pinfunction "1_1") (pintype "passive"))
      (node (ref "SW21") (pin "1") (pinfunction "1_1") (pintype "passive"))
      (node (ref "U5") (pin "3") (pinfunction "D4_3") (pintype "input"))
    )
    (net (code "23") (name "BUTTON22") (class "Default")
      (node (ref "R54") (pin "1") (pinfunction "1_1") (pintype "passive"))
      (node (ref "SW22") (pin "1") (pinfunction "1_1") (pintype "passive"))
      (node (ref "U5") (pin "4") (pinfunction "D5_4") (pintype "input"))
    )
    (net (code "24") (name "BUTTON23") (class "Default")
      (node (ref "R55") (pin "1") (pinfunction "1_1") (pintype "passive"))
      (node (ref "SW23") (pin "1") (pinfunction "1_1") (pintype "passive"))
      (node (ref "U5") (pin "5") (pinfunction "D6_5") (pintype "input"))
    )
    (net (code "25") (name "BUTTON24") (class "Default")
      (node (ref "R56") (pin "1") (pinfunction "1_1") (pintype "passive"))
      (node (ref "SW24") (pin "1") (pinfunction "1_1") (pintype "passive"))
      (node (ref "U5") (pin "6") (pinfunction "D7_6") (pintype "input"))
    )
    (net (code "26") (name "BUTTON25") (class "Default")
      (node (ref "R73") (pin "1") (pinfunction "1_1") (pintype "passive"))
      (node (ref "SW25") (pin "1") (pinfunction "1_1") (pintype "passive"))
      (node (ref "U7") (pin "11") (pinfunction "D0_11") (pintype "input"))
    )
    (net (code "27") (name "BUTTON26") (class "Default")
      (node (ref "R74") (pin "1") (pinfunction "1_1") (pintype "passive"))
      (node (ref "SW26") (pin "1") (pinfunction "1_1") (pintype "passive"))
      (node (ref "U7") (pin "12") (pinfunction "D1_12") (pintype "input"))
    )
    (net (code "28") (name "BUTTON27") (class "Default")
      (node (ref "R75") (pin "1") (pinfunction "1_1") (pintype "passive"))
      (node (ref "SW27") (pin "1") (pinfunction "1_1") (pintype "passive"))
      (node (ref "U7") (pin "13") (pinfunction "D2_13") (pintype "input"))
    )
    (net (code "29") (name "BUTTON28") (class "Default")
      (node (ref "R76") (pin "1") (pinfunction "1_1") (pintype "passive"))
      (node (ref "SW28") (pin "1") (pinfunction "1_1") (pintype "passive"))
      (node (ref "U7") (pin "14") (pinfunction "D3_14") (pintype "input"))
    )
    (net (code "30") (name "BUTTON29") (class "Default")
      (node (ref "R77") (pin "1") (pinfunction "1_1") (pintype "passive"))
      (node (ref "SW29") (pin "1") (pinfunction "1_1") (pintype "passive"))
      (node (ref "U7") (pin "3") (pinfunction "D4_3") (pintype "input"))
    )
    (net (code "31") (name "BUTTON30") (class "Default")
      (node (ref "R78") (pin "1") (pinfunction "1_1") (pintype "passive"))
      (node (ref "SW30") (pin "1") (pinfunction "1_1") (pintype "passive"))
      (node (ref "U7") (pin "4") (pinfunction "D5_4") (pintype "input"))
    )
    (net (code "32") (name "BUTTON31") (class "Default")
      (node (ref "R79") (pin "1") (pinfunction "1_1") (pintype "passive"))
      (node (ref "SW31") (pin "1") (pinfunction "1_1") (pintype "passive"))
      (node (ref "U7") (pin "5") (pinfunction "D6_5") (pintype "input"))
    )
    (net (code "33") (name "BUTTON32") (class "Default")
      (node (ref "R80") (pin "1") (pinfunction "1_1") (pintype "passive"))
      (node (ref "SW32") (pin "1") (pinfunction "1_1") (pintype "passive"))
      (node (ref "U7") (pin "6") (pinfunction "D7_6") (pintype "input"))
    )
    (net (code "34") (name "GND") (class "Default")
      (node (ref "C1") (pin "2") (pinfunction "2_2") (pintype "passive"))
      (node (ref "C2") (pin "2") (pinfunction "2_2") (pintype "passive"))
      (node (ref "C3") (pin "2") (pinfunction "2_2") (pintype "passive"))
      (node (ref "C4") (pin "2") (pinfunction "2_2") (pintype "passive"))
      (node (ref "C5") (pin "2") (pinfunction "2_2") (pintype "passive"))
      (node (ref "C6") (pin "2") (pinfunction "2_2") (pintype "passive"))
      (node (ref "C7") (pin "2") (pinfunction "2_2") (pintype "passive"))
      (node (ref "C8") (pin "2") (pinfunction "2_2") (pintype "passive"))
      (node (ref "CONN1") (pin "1") (pinfunction "1_1") (pintype "passive"))
      (node (ref "SW1") (pin "3") (pinfunction "2_3") (pintype "passive"))
      (node (ref "SW10") (pin "3") (pinfunction "2_3") (pintype "passive"))
      (node (ref "SW11") (pin "3") (pinfunction "2_3") (pintype "passive"))
      (node (ref "SW12") (pin "3") (pinfunction "2_3") (pintype "passive"))
      (node (ref "SW13") (pin "3") (pinfunction "2_3") (pintype "passive"))
      (node (ref "SW14") (pin "3") (pinfunction "2_3") (pintype "passive"))
      (node (ref "SW15") (pin "3") (pinfunction "2_3") (pintype "passive"))
      (node (ref "SW16") (pin "3") (pinfunction "2_3") (pintype "passive"))
      (node (ref "SW17") (pin "3") (pinfunction "2_3") (pintype "passive"))
      (node (ref "SW18") (pin "3") (pinfunction "2_3") (pintype "passive"))
      (node (ref "SW19") (pin "3") (pinfunction "2_3") (pintype "passive"))
      (node (ref "SW2") (pin "3") (pinfunction "2_3") (pintype "passive"))
      (node (ref "SW20") (pin "3") (pinfunction "2_3") (pintype "passive"))
      (node (ref "SW21") (pin "3") (pinfunction "2_3") (pintype "passive"))
      (node (ref "SW22") (pin "3") (pinfunction "2_3") (pintype "passive"))
      (node (ref "SW23") (pin "3") (pinfunction "2_3") (pintype "passive"))
      (node (ref "SW24") (pin "3") (pinfunction "2_3") (pintype "passive"))
      (node (ref "SW25") (pin "3") (pinfunction "2_3") (pintype "passive"))
      (node (ref "SW26") (pin "3") (pinfunction "2_3") (pintype "passive"))
      (node (ref "SW27") (pin "3") (pinfunction "2_3") (pintype "passive"))
      (node (ref "SW28") (pin "3") (pinfunction "2_3") (pintype "passive"))
      (node (ref "SW29") (pin "3") (pinfunction "2_3") (pintype "passive"))
      (node (ref "SW3") (pin "3") (pinfunction "2_3") (pintype "passive"))
      (node (ref "SW30") (pin "3") (pinfunction "2_3") (pintype "passive"))
      (node (ref "SW31") (pin "3") (pinfunction "2_3") (pintype "passive"))
      (node (ref "SW32") (pin "3") (pinfunction "2_3") (pintype "passive"))
      (node (ref "SW4") (pin "3") (pinfunction "2_3") (pintype "passive"))
      (node (ref "SW5") (pin "3") (pinfunction "2_3") (pintype "passive"))
      (node (ref "SW6") (pin "3") (pinfunction "2_3") (pintype "passive"))
      (node (ref "SW7") (pin "3") (pinfunction "2_3") (pintype "passive"))
      (node (ref "SW8") (pin "3") (pinfunction "2_3") (pintype "passive"))
      (node (ref "SW9") (pin "3") (pinfunction "2_3") (pintype "passive"))
      (node (ref "U1") (pin "15") (pinfunction "~{CE}_15") (pintype "input"))
      (node (ref "U1") (pin "8") (pinfunction "GND_8") (pintype "power_in"))
      (node (ref "U2") (pin "10") (pinfunction "GND_10") (pintype "power_in"))
      (node (ref "U2") (pin "11") (pinfunction "GND_11") (pintype "power_in"))
      (node (ref "U2") (pin "19") (pinfunction "GND_19") (pintype "power_in"))
      (node (ref "U3") (pin "15") (pinfunction "~{CE}_15") (pintype "input"))
      (node (ref "U3") (pin "8") (pinfunction "GND_8") (pintype "power_in"))
      (node (ref "U4") (pin "10") (pinfunction "GND_10") (pintype "power_in"))
      (node (ref "U4") (pin "11") (pinfunction "GND_11") (pintype "power_in"))
      (node (ref "U4") (pin "19") (pinfunction "GND_19") (pintype "power_in"))
      (node (ref "U5") (pin "15") (pinfunction "~{CE}_15") (pintype "input"))
      (node (ref "U5") (pin "8") (pinfunction "GND_8") (pintype "power_in"))
      (node (ref "U6") (pin "10") (pinfunction "GND_10") (pintype "power_in"))
      (node (ref "U6") (pin "11") (pinfunction "GND_11") (pintype "power_in"))
      (node (ref "U6") (pin "19") (pinfunction "GND_19") (pintype "power_in"))
      (node (ref "U7") (pin "15") (pinfunction "~{CE}_15") (pintype "input"))
      (node (ref "U7") (pin "8") (pinfunction "GND_8") (pintype "power_in"))
      (node (ref "U8") (pin "10") (pinfunction "GND_10") (pintype "power_in"))
      (node (ref "U8") (pin "11") (pinfunction "GND_11") (pintype "power_in"))
      (node (ref "U8") (pin "19") (pinfunction "GND_19") (pintype "power_in"))
    )
    (net (code "35") (name "LED1") (class "Default")
      (node (ref "R17") (pin "1") (pinfunction "1_1") (pintype "passive"))
      (node (ref "R9") (pin "2") (pinfunction "2_2") (pintype "passive"))
      (node (ref "U2") (pin "14") (pinfunction "D4_14") (pintype "output"))
    )
    (net (code "36") (name "LED2") (class "Default")
      (node (ref "R10") (pin "2") (pinfunction "2_2") (pintype "passive"))
      (node (ref "R18") (pin "1") (pinfunction "1_1") (pintype "passive"))
      (node (ref "U2") (pin "15") (pinfunction "D5_15") (pintype "output"))
    )
    (net (code "37") (name "LED3") (class "Default")
      (node (ref "R11") (pin "2") (pinfunction "2_2") (pintype "passive"))
      (node (ref "R19") (pin "1") (pinfunction "1_1") (pintype "passive"))
      (node (ref "U2") (pin "16") (pinfunction "D6_16") (pintype "output"))
    )
    (net (code "38") (name "LED4") (class "Default")
      (node (ref "R12") (pin "2") (pinfunction "2_2") (pintype "passive"))
      (node (ref "R20") (pin "1") (pinfunction "1_1") (pintype "passive"))
      (node (ref "U2") (pin "17") (pinfunction "D7_17") (pintype "output"))
    )
    (net (code "39") (name "LED5") (class "Default")
      (node (ref "R13") (pin "2") (pinfunction "2_2") (pintype "passive"))
      (node (ref "R21") (pin "1") (pinfunction "1_1") (pintype "passive"))
      (node (ref "U2") (pin "4") (pinfunction "D0_4") (pintype "output"))
    )
    (net (code "40") (name "LED6") (class "Default")
      (node (ref "R14") (pin "2") (pinfunction "2_2") (pintype "passive"))
      (node (ref "R22") (pin "1") (pinfunction "1_1") (pintype "passive"))
      (node (ref "U2") (pin "5") (pinfunction "D1_5") (pintype "output"))
    )
    (net (code "41") (name "LED7") (class "Default")
      (node (ref "R15") (pin "2") (pinfunction "2_2") (pintype "passive"))
      (node (ref "R23") (pin "1") (pinfunction "1_1") (pintype "passive"))
      (node (ref "U2") (pin "6") (pinfunction "D2_6") (pintype "output"))
    )
    (net (code "42") (name "LED8") (class "Default")
      (node (ref "R16") (pin "2") (pinfunction "2_2") (pintype "passive"))
      (node (ref "R24") (pin "1") (pinfunction "1_1") (pintype "passive"))
      (node (ref "U2") (pin "7") (pinfunction "D3_7") (pintype "output"))
    )
    (net (code "43") (name "LED9") (class "Default")
      (node (ref "R33") (pin "2") (pinfunction "2_2") (pintype "passive"))
      (node (ref "R41") (pin "1") (pinfunction "1_1") (pintype "passive"))
      (node (ref "U4") (pin "14") (pinfunction "D4_14") (pintype "output"))
    )
    (net (code "44") (name "LED10") (class "Default")
      (node (ref "R34") (pin "2") (pinfunction "2_2") (pintype "passive"))
      (node (ref "R42") (pin "1") (pinfunction "1_1") (pintype "passive"))
      (node (ref "U4") (pin "15") (pinfunction "D5_15") (pintype "output"))
    )
    (net (code "45") (name "LED11") (class "Default")
      (node (ref "R35") (pin "2") (pinfunction "2_2") (pintype "passive"))
      (node (ref "R43") (pin "1") (pinfunction "1_1") (pintype "passive"))
      (node (ref "U4") (pin "16") (pinfunction "D6_16") (pintype "output"))
    )
    (net (code "46") (name "LED12") (class "Default")
      (node (ref "R36") (pin "2") (pinfunction "2_2") (pintype "passive"))
      (node (ref "R44") (pin "1") (pinfunction "1_1") (pintype "passive"))
      (node (ref "U4") (pin "17") (pinfunction "D7_17") (pintype "output"))
    )
    (net (code "47") (name "LED13") (class "Default")
      (node (ref "R37") (pin "2") (pinfunction "2_2") (pintype "passive"))
      (node (ref "R45") (pin "1") (pinfunction "1_1") (pintype "passive"))
      (node (ref "U4") (pin "4") (pinfunction "D0_4") (pintype "output"))
    )
    (net (code "48") (name "LED14") (class "Default")
      (node (ref "R38") (pin "2") (pinfunction "2_2") (pintype "passive"))
      (node (ref "R46") (pin "1") (pinfunction "1_1") (pintype "passive"))
      (node (ref "U4") (pin "5") (pinfunction "D1_5") (pintype "output"))
    )
    (net (code "49") (name "LED15") (class "Default")
      (node (ref "R39") (pin "2") (pinfunction "2_2") (pintype "passive"))
      (node (ref "R47") (pin "1") (pinfunction "1_1") (pintype "passive"))
      (node (ref "U4") (pin "6") (pinfunction "D2_6") (pintype "output"))
    )
    (net (code "50") (name "LED16") (class "Default")
      (node (ref "R40") (pin "2") (pinfunction "2_2") (pintype "passive"))
      (node (ref "R48") (pin "1") (pinfunction "1_1") (pintype "passive"))
      (node (ref "U4") (pin "7") (pinfunction "D3_7") (pintype "output"))
    )
    (net (code "51") (name "LED17") (class "Default")
      (node (ref "R57") (pin "2") (pinfunction "2_2") (pintype "passive"))
      (node (ref "R65") (pin "1") (pinfunction "1_1") (pintype "passive"))
      (node (ref "U6") (pin "14") (pinfunction "D4_14") (pintype "output"))
    )
    (net (code "52") (name "LED18") (class "Default")
      (node (ref "R58") (pin "2") (pinfunction "2_2") (pintype "passive"))
      (node (ref "R66") (pin "1") (pinfunction "1_1") (pintype "passive"))
      (node (ref "U6") (pin "15") (pinfunction "D5_15") (pintype "output"))
    )
    (net (code "53") (name "LED19") (class "Default")
      (node (ref "R59") (pin "2") (pinfunction "2_2") (pintype "passive"))
      (node (ref "R67") (pin "1") (pinfunction "1_1") (pintype "passive"))
      (node (ref "U6") (pin "16") (pinfunction "D6_16") (pintype "output"))
    )
    (net (code "54") (name "LED20") (class "Default")
      (node (ref "R60") (pin "2") (pinfunction "2_2") (pintype "passive"))
      (node (ref "R68") (pin "1") (pinfunction "1_1") (pintype "passive"))
      (node (ref "U6") (pin "17") (pinfunction "D7_17") (pintype "output"))
    )
    (net (code "55") (name "LED21") (class "Default")
      (node (ref "R61") (pin "2") (pinfunction "2_2") (pintype "passive"))
      (node (ref "R69") (pin "1") (pinfunction "1_1") (pintype "passive"))
      (node (ref "U6") (pin "4") (pinfunction "D0_4") (pintype "output"))
    )
    (net (code "56") (name "LED22") (class "Default")
      (node (ref "R62") (pin "2") (pinfunction "2_2") (pintype "passive"))
      (node (ref "R70") (pin "1") (pinfunction "1_1") (pintype "passive"))
      (node (ref "U6") (pin "5") (pinfunction "D1_5") (pintype "output"))
    )
    (net (code "57") (name "LED23") (class "Default")
      (node (ref "R63") (pin "2") (pinfunction "2_2") (pintype "passive"))
      (node (ref "R71") (pin "1") (pinfunction "1_1") (pintype "passive"))
      (node (ref "U6") (pin "6") (pinfunction "D2_6") (pintype "output"))
    )
    (net (code "58") (name "LED24") (class "Default")
      (node (ref "R64") (pin "2") (pinfunction "2_2") (pintype "passive"))
      (node (ref "R72") (pin "1") (pinfunction "1_1") (pintype "passive"))
      (node (ref "U6") (pin "7") (pinfunction "D3_7") (pintype "output"))
    )
    (net (code "59") (name "LED25") (class "Default")
      (node (ref "R81") (pin "2") (pinfunction "2_2") (pintype "passive"))
      (node (ref "R89") (pin "1") (pinfunction "1_1") (pintype "passive"))
      (node (ref "U8") (pin "14") (pinfunction "D4_14") (pintype "output"))
    )
    (net (code "60") (name "LED26") (class "Default")
      (node (ref "R82") (pin "2") (pinfunction "2_2") (pintype "passive"))
      (node (ref "R90") (pin "1") (pinfunction "1_1") (pintype "passive"))
      (node (ref "U8") (pin "15") (pinfunction "D5_15") (pintype "output"))
    )
    (net (code "61") (name "LED27") (class "Default")
      (node (ref "R83") (pin "2") (pinfunction "2_2") (pintype "passive"))
      (node (ref "R91") (pin "1") (pinfunction "1_1") (pintype "passive"))
      (node (ref "U8") (pin "16") (pinfunction "D6_16") (pintype "output"))
    )
    (net (code "62") (name "LED28") (class "Default")
      (node (ref "R84") (pin "2") (pinfunction "2_2") (pintype "passive"))
      (node (ref "R92") (pin "1") (pinfunction "1_1") (pintype "passive"))
      (node (ref "U8") (pin "17") (pinfunction "D7_17") (pintype "output"))
    )
    (net (code "63") (name "LED29") (class "Default")
      (node (ref "R85") (pin "2") (pinfunction "2_2") (pintype "passive"))
      (node (ref "R93") (pin "1") (pinfunction "1_1") (pintype "passive"))
      (node (ref "U8") (pin "4") (pinfunction "D0_4") (pintype "output"))
    )
    (net (code "64") (name "LED30") (class "Default")
      (node (ref "R86") (pin "2") (pinfunction "2_2") (pintype "passive"))
      (node (ref "R94") (pin "1") (pinfunction "1_1") (pintype "passive"))
      (node (ref "U8") (pin "5") (pinfunction "D1_5") (pintype "output"))
    )
    (net (code "65") (name "LED31") (class "Default")
      (node (ref "R87") (pin "2") (pinfunction "2_2") (pintype "passive"))
      (node (ref "R95") (pin "1") (pinfunction "1_1") (pintype "passive"))
      (node (ref "U8") (pin "6") (pinfunction "D2_6") (pintype "output"))
    )
    (net (code "66") (name "LED32") (class "Default")
      (node (ref "R88") (pin "2") (pinfunction "2_2") (pintype "passive"))
      (node (ref "R96") (pin "1") (pinfunction "1_1") (pintype "passive"))
      (node (ref "U8") (pin "7") (pinfunction "D3_7") (pintype "output"))
    )
    (net (code "67") (name "Net-(SW1A-C)") (class "Default")
      (node (ref "R9") (pin "1") (pinfunction "1_1") (pintype "passive"))
      (node (ref "SW1") (pin "6-C") (pinfunction "C_6-C") (pintype "passive"))
    )
    (net (code "68") (name "Net-(SW2A-C)") (class "Default")
      (node (ref "R10") (pin "1") (pinfunction "1_1") (pintype "passive"))
      (node (ref "SW2") (pin "6-C") (pinfunction "C_6-C") (pintype "passive"))
    )
    (net (code "69") (name "Net-(SW3A-C)") (class "Default")
      (node (ref "R11") (pin "1") (pinfunction "1_1") (pintype "passive"))
      (node (ref "SW3") (pin "6-C") (pinfunction "C_6-C") (pintype "passive"))
    )
    (net (code "70") (name "Net-(SW4A-C)") (class "Default")
      (node (ref "R12") (pin "1") (pinfunction "1_1") (pintype "passive"))
      (node (ref "SW4") (pin "6-C") (pinfunction "C_6-C") (pintype "passive"))
    )
    (net (code "71") (name "Net-(SW5A-C)") (class "Default")
      (node (ref "R13") (pin "1") (pinfunction "1_1") (pintype "passive"))
      (node (ref "SW5") (pin "6-C") (pinfunction "C_6-C") (pintype "passive"))
    )
    (net (code "72") (name "Net-(SW6A-C)") (class "Default")
      (node (ref "R14") (pin "1") (pinfunction "1_1") (pintype "passive"))
      (node (ref "SW6") (pin "6-C") (pinfunction "C_6-C") (pintype "passive"))
    )
    (net (code "73") (name "Net-(SW7A-C)") (class "Default")
      (node (ref "R15") (pin "1") (pinfunction "1_1") (pintype "passive"))
      (node (ref "SW7") (pin "6-C") (pinfunction "C_6-C") (pintype "passive"))
    )
    (net (code "74") (name "Net-(SW8A-C)") (class "Default")
      (node (ref "R16") (pin "1") (pinfunction "1_1") (pintype "passive"))
      (node (ref "SW8") (pin "6-C") (pinfunction "C_6-C") (pintype "passive"))
    )
    (net (code "75") (name "Net-(SW9A-C)") (class "Default")
      (node (ref "R33") (pin "1") (pinfunction "1_1") (pintype "passive"))
      (node (ref "SW9") (pin "6-C") (pinfunction "C_6-C") (pintype "passive"))
    )
    (net (code "76") (name "Net-(SW10A-C)") (class "Default")
      (node (ref "R34") (pin "1") (pinfunction "1_1") (pintype "passive"))
      (node (ref "SW10") (pin "6-C") (pinfunction "C_6-C") (pintype "passive"))
    )
    (net (code "77") (name "Net-(SW11A-C)") (class "Default")
      (node (ref "R35") (pin "1") (pinfunction "1_1") (pintype "passive"))
      (node (ref "SW11") (pin "6-C") (pinfunction "C_6-C") (pintype "passive"))
    )
    (net (code "78") (name "Net-(SW12A-C)") (class "Default")
      (node (ref "R36") (pin "1") (pinfunction "1_1") (pintype "passive"))
      (node (ref "SW12") (pin "6-C") (pinfunction "C_6-C") (pintype "passive"))
    )
    (net (code "79") (name "Net-(SW13A-C)") (class "Default")
      (node (ref "R37") (pin "1") (pinfunction "1_1") (pintype "passive"))
      (node (ref "SW13") (pin "6-C") (pinfunction "C_6-C") (pintype "passive"))
    )
    (net (code "80") (name "Net-(SW14A-C)") (class "Default")
      (node (ref "R38") (pin "1") (pinfunction "1_1") (pintype "passive"))
      (node (ref "SW14") (pin "6-C") (pinfunction "C_6-C") (pintype "passive"))
    )
    (net (code "81") (name "Net-(SW15A-C)") (class "Default")
      (node (ref "R39") (pin "1") (pinfunction "1_1") (pintype "passive"))
      (node (ref "SW15") (pin "6-C") (pinfunction "C_6-C") (pintype "passive"))
    )
    (net (code "82") (name "Net-(SW16A-C)") (class "Default")
      (node (ref "R40") (pin "1") (pinfunction "1_1") (pintype "passive"))
      (node (ref "SW16") (pin "6-C") (pinfunction "C_6-C") (pintype "passive"))
    )
    (net (code "83") (name "Net-(SW17A-C)") (class "Default")
      (node (ref "R57") (pin "1") (pinfunction "1_1") (pintype "passive"))
      (node (ref "SW17") (pin "6-C") (pinfunction "C_6-C") (pintype "passive"))
    )
    (net (code "84") (name "Net-(SW18A-C)") (class "Default")
      (node (ref "R58") (pin "1") (pinfunction "1_1") (pintype "passive"))
      (node (ref "SW18") (pin "6-C") (pinfunction "C_6-C") (pintype "passive"))
    )
    (net (code "85") (name "Net-(SW19A-C)") (class "Default")
      (node (ref "R59") (pin "1") (pinfunction "1_1") (pintype "passive"))
      (node (ref "SW19") (pin "6-C") (pinfunction "C_6-C") (pintype "passive"))
    )
    (net (code "86") (name "Net-(SW20A-C)") (class "Default")
      (node (ref "R60") (pin "1") (pinfunction "1_1") (pintype "passive"))
      (node (ref "SW20") (pin "6-C") (pinfunction "C_6-C") (pintype "passive"))
    )
    (net (code "87") (name "Net-(SW21A-C)") (class "Default")
      (node (ref "R61") (pin "1") (pinfunction "1_1") (pintype "passive"))
      (node (ref "SW21") (pin "6-C") (pinfunction "C_6-C") (pintype "passive"))
    )
    (net (code "88") (name "Net-(SW22A-C)") (class "Default")
      (node (ref "R62") (pin "1") (pinfunction "1_1") (pintype "passive"))
      (node (ref "SW22") (pin "6-C") (pinfunction "C_6-C") (pintype "passive"))
    )
    (net (code "89") (name "Net-(SW23A-C)") (class "Default")
      (node (ref "R63") (pin "1") (pinfunction "1_1") (pintype "passive"))
      (node (ref "SW23") (pin "6-C") (pinfunction "C_6-C") (pintype "passive"))
    )
    (net (code "90") (name "Net-(SW24A-C)") (class "Default")
      (node (ref "R64") (pin "1") (pinfunction "1_1") (pintype "passive"))
      (node (ref "SW24") (pin "6-C") (pinfunction "C_6-C") (pintype "passive"))
    )
    (net (code "91") (name "Net-(SW25A-C)") (class "Default")
      (node (ref "R81") (pin "1") (pinfunction "1_1") (pintype "passive"))
      (node (ref "SW25") (pin "6-C") (pinfunction "C_6-C") (pintype "passive"))
    )
    (net (code "92") (name "Net-(SW26A-C)") (class "Default")
      (node (ref "R82") (pin "1") (pinfunction "1_1") (pintype "passive"))
      (node (ref "SW26") (pin "6-C") (pinfunction "C_6-C") (pintype "passive"))
    )
    (net (code "93") (name "Net-(SW27A-C)") (class "Default")
      (node (ref "R83") (pin "1") (pinfunction "1_1") (pintype "passive"))
      (node (ref "SW27") (pin "6-C") (pinfunction "C_6-C") (pintype "passive"))
    )
    (net (code "94") (name "Net-(SW28A-C)") (class "Default")
      (node (ref "R84") (pin "1") (pinfunction "1_1") (pintype "passive"))
      (node (ref "SW28") (pin "6-C") (pinfunction "C_6-C") (pintype "passive"))
    )
    (net (code "95") (name "Net-(SW29A-C)") (class "Default")
      (node (ref "R85") (pin "1") (pinfunction "1_1") (pintype "passive"))
      (node (ref "SW29") (pin "6-C") (pinfunction "C_6-C") (pintype "passive"))
    )
    (net (code "96") (name "Net-(SW30A-C)") (class "Default")
      (node (ref "R86") (pin "1") (pinfunction "1_1") (pintype "passive"))
      (node (ref "SW30") (pin "6-C") (pinfunction "C_6-C") (pintype "passive"))
    )
    (net (code "97") (name "Net-(SW31A-C)") (class "Default")
      (node (ref "R87") (pin "1") (pinfunction "1_1") (pintype "passive"))
      (node (ref "SW31") (pin "6-C") (pinfunction "C_6-C") (pintype "passive"))
    )
    (net (code "98") (name "Net-(SW32A-C)") (class "Default")
      (node (ref "R88") (pin "1") (pinfunction "1_1") (pintype "passive"))
      (node (ref "SW32") (pin "6-C") (pinfunction "C_6-C") (pintype "passive"))
    )
    (net (code "99") (name "SR_IN_CLOCK") (class "Default")
      (node (ref "CONN1") (pin "5") (pinfunction "5_5") (pintype "passive"))
      (node (ref "U1") (pin "2") (pinfunction "CP_2") (pintype "bidirectional"))
      (node (ref "U3") (pin "2") (pinfunction "CP_2") (pintype "bidirectional"))
      (node (ref "U5") (pin "2") (pinfunction "CP_2") (pintype "bidirectional"))
      (node (ref "U7") (pin "2") (pinfunction "CP_2") (pintype "bidirectional"))
    )
    (net (code "100") (name "SR_IN_DAISY_OUT_1") (class "Default")
      (node (ref "U5") (pin "9") (pinfunction "Q7_9") (pintype "output"))
      (node (ref "U7") (pin "10") (pinfunction "DS_10") (pintype "bidirectional"))
    )
    (net (code "101") (name "SR_IN_DAISY_OUT_2") (class "Default")
      (node (ref "U3") (pin "9") (pinfunction "Q7_9") (pintype "output"))
      (node (ref "U5") (pin "10") (pinfunction "DS_10") (pintype "bidirectional"))
    )
    (net (code "102") (name "SR_IN_DAISY_OUT_3") (class "Default")
      (node (ref "U1") (pin "9") (pinfunction "Q7_9") (pintype "output"))
      (node (ref "U3") (pin "10") (pinfunction "DS_10") (pintype "bidirectional"))
    )
    (net (code "103") (name "SR_IN_DATA") (class "Default")
      (node (ref "CONN1") (pin "6") (pinfunction "6_6") (pintype "passive"))
      (node (ref "U7") (pin "9") (pinfunction "Q7_9") (pintype "output"))
    )
    (net (code "104") (name "SR_IN_LATCH") (class "Default")
      (node (ref "CONN1") (pin "4") (pinfunction "4_4") (pintype "passive"))
      (node (ref "U1") (pin "1") (pinfunction "~{PL}_1") (pintype "input"))
      (node (ref "U3") (pin "1") (pinfunction "~{PL}_1") (pintype "input"))
      (node (ref "U5") (pin "1") (pinfunction "~{PL}_1") (pintype "input"))
      (node (ref "U7") (pin "1") (pinfunction "~{PL}_1") (pintype "input"))
    )
    (net (code "105") (name "SR_OUT_CLOCK") (class "Default")
      (node (ref "CONN1") (pin "7") (pinfunction "7_7") (pintype "passive"))
      (node (ref "U2") (pin "13") (pinfunction "SRCK_13") (pintype "input"))
      (node (ref "U4") (pin "13") (pinfunction "SRCK_13") (pintype "input"))
      (node (ref "U6") (pin "13") (pinfunction "SRCK_13") (pintype "input"))
      (node (ref "U8") (pin "13") (pinfunction "SRCK_13") (pintype "input"))
    )
    (net (code "106") (name "SR_OUT_DAISY_OUT_1") (class "Default")
      (node (ref "U6") (pin "3") (pinfunction "SER_IN_3") (pintype "input"))
      (node (ref "U8") (pin "18") (pinfunction "SER_OUT_18") (pintype "output"))
    )
    (net (code "107") (name "SR_OUT_DAISY_OUT_2") (class "Default")
      (node (ref "U4") (pin "3") (pinfunction "SER_IN_3") (pintype "input"))
      (node (ref "U6") (pin "18") (pinfunction "SER_OUT_18") (pintype "output"))
    )
    (net (code "108") (name "SR_OUT_DAISY_OUT_3") (class "Default")
      (node (ref "U2") (pin "3") (pinfunction "SER_IN_3") (pintype "input"))
      (node (ref "U4") (pin "18") (pinfunction "SER_OUT_18") (pintype "output"))
    )
    (net (code "109") (name "SR_OUT_DATA") (class "Default")
      (node (ref "CONN1") (pin "9") (pinfunction "9_9") (pintype "passive"))
      (node (ref "U8") (pin "3") (pinfunction "SER_IN_3") (pintype "input"))
    )
    (net (code "110") (name "SR_OUT_LATCH") (class "Default")
      (node (ref "CONN1") (pin "8") (pinfunction "8_8") (pintype "passive"))
      (node (ref "U2") (pin "12") (pinfunction "RCK_12") (pintype "input"))
      (node (ref "U4") (pin "12") (pinfunction "RCK_12") (pintype "input"))
      (node (ref "U6") (pin "12") (pinfunction "RCK_12") (pintype "input"))
      (node (ref "U8") (pin "12") (pinfunction "RCK_12") (pintype "input"))
    )
    (net (code "111") (name "SR_OUT_OE") (class "Default")
      (node (ref "CONN1") (pin "10") (pinfunction "10_10") (pintype "passive"))
      (node (ref "U2") (pin "9") (pinfunction "~{G/OE}_9") (pintype "input"))
      (node (ref "U4") (pin "9") (pinfunction "~{G/OE}_9") (pintype "input"))
      (node (ref "U6") (pin "9") (pinfunction "~{G/OE}_9") (pintype "input"))
      (node (ref "U8") (pin "9") (pinfunction "~{G/OE}_9") (pintype "input"))
    )
    (net (code "112") (name "unconnected-(U1-DS-Pad10)") (class "Default")
      (node (ref "U1") (pin "10") (pinfunction "DS_10") (pintype "bidirectional"))
    )
    (net (code "113") (name "unconnected-(U1-~{Q7}-Pad7)") (class "Default")
      (node (ref "U1") (pin "7") (pinfunction "~{Q7}_7") (pintype "output"))
    )
    (net (code "114") (name "unconnected-(U2-SER_OUT-Pad18)") (class "Default")
      (node (ref "U2") (pin "18") (pinfunction "SER_OUT_18") (pintype "output"))
    )
    (net (code "115") (name "unconnected-(U3-~{Q7}-Pad7)") (class "Default")
      (node (ref "U3") (pin "7") (pinfunction "~{Q7}_7") (pintype "output"))
    )
    (net (code "116") (name "unconnected-(U5-~{Q7}-Pad7)") (class "Default")
      (node (ref "U5") (pin "7") (pinfunction "~{Q7}_7") (pintype "output"))
    )
    (net (code "117") (name "unconnected-(U7-~{Q7}-Pad7)") (class "Default")
      (node (ref "U7") (pin "7") (pinfunction "~{Q7}_7") (pintype "output"))
    )
  )
)
